# isg_eos_control_board_xem3001.net
KiCad netlist of a schematic drawn in Altium Designer
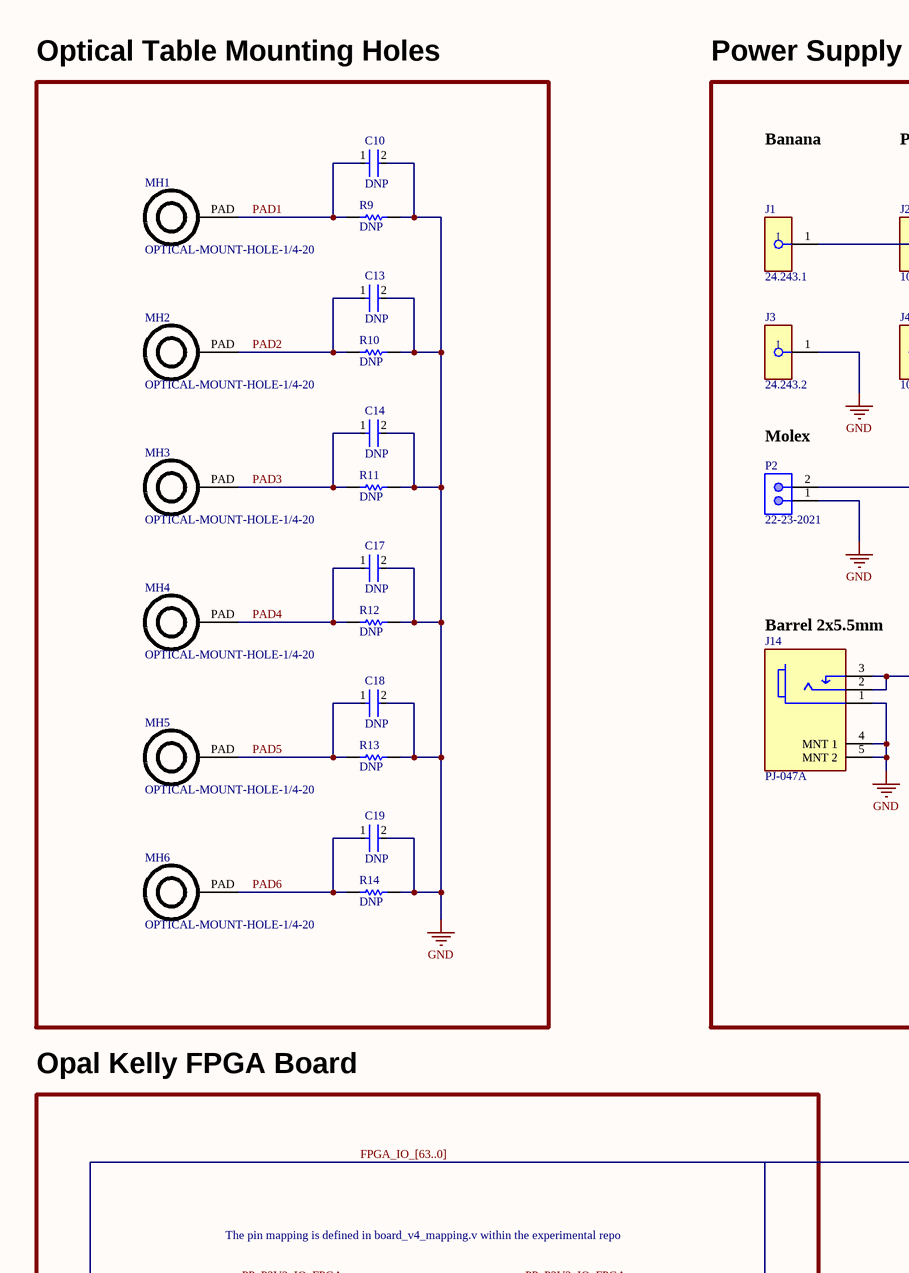
[diagram p0: isg_eos_control_board_xem3001.SchDoc, top left]
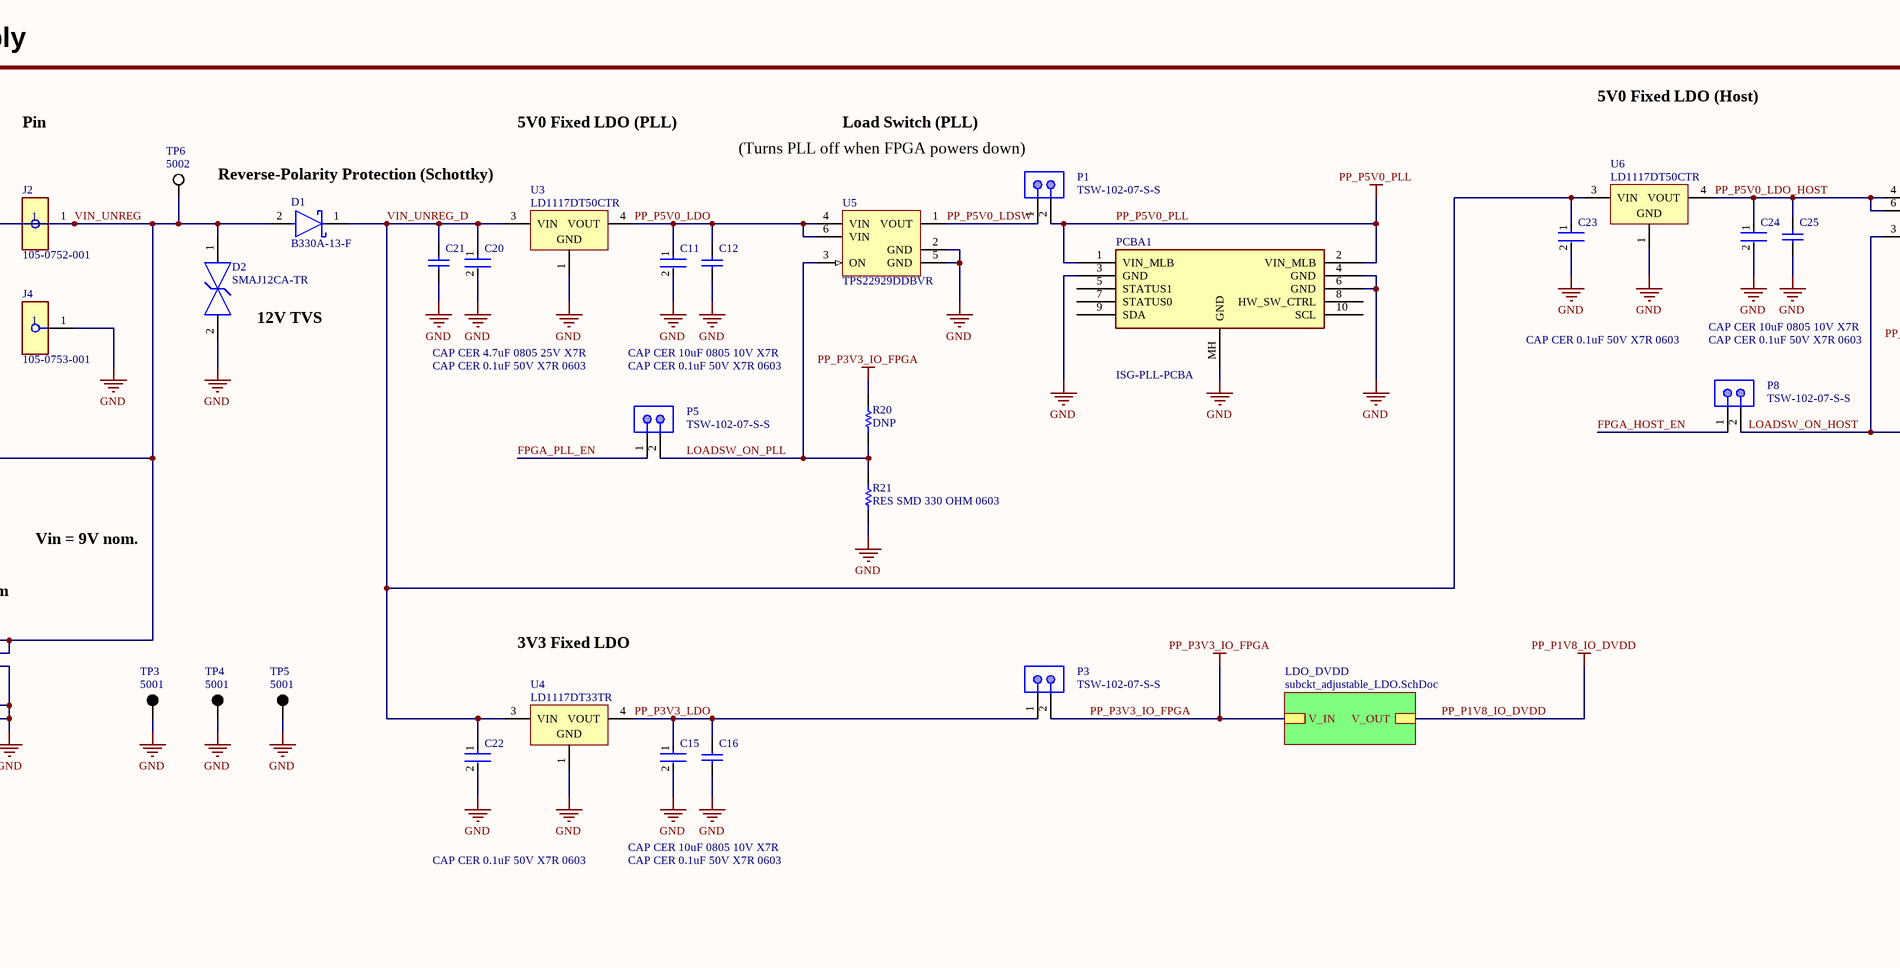
[diagram p1: isg_eos_control_board_xem3001.SchDoc, top middle]
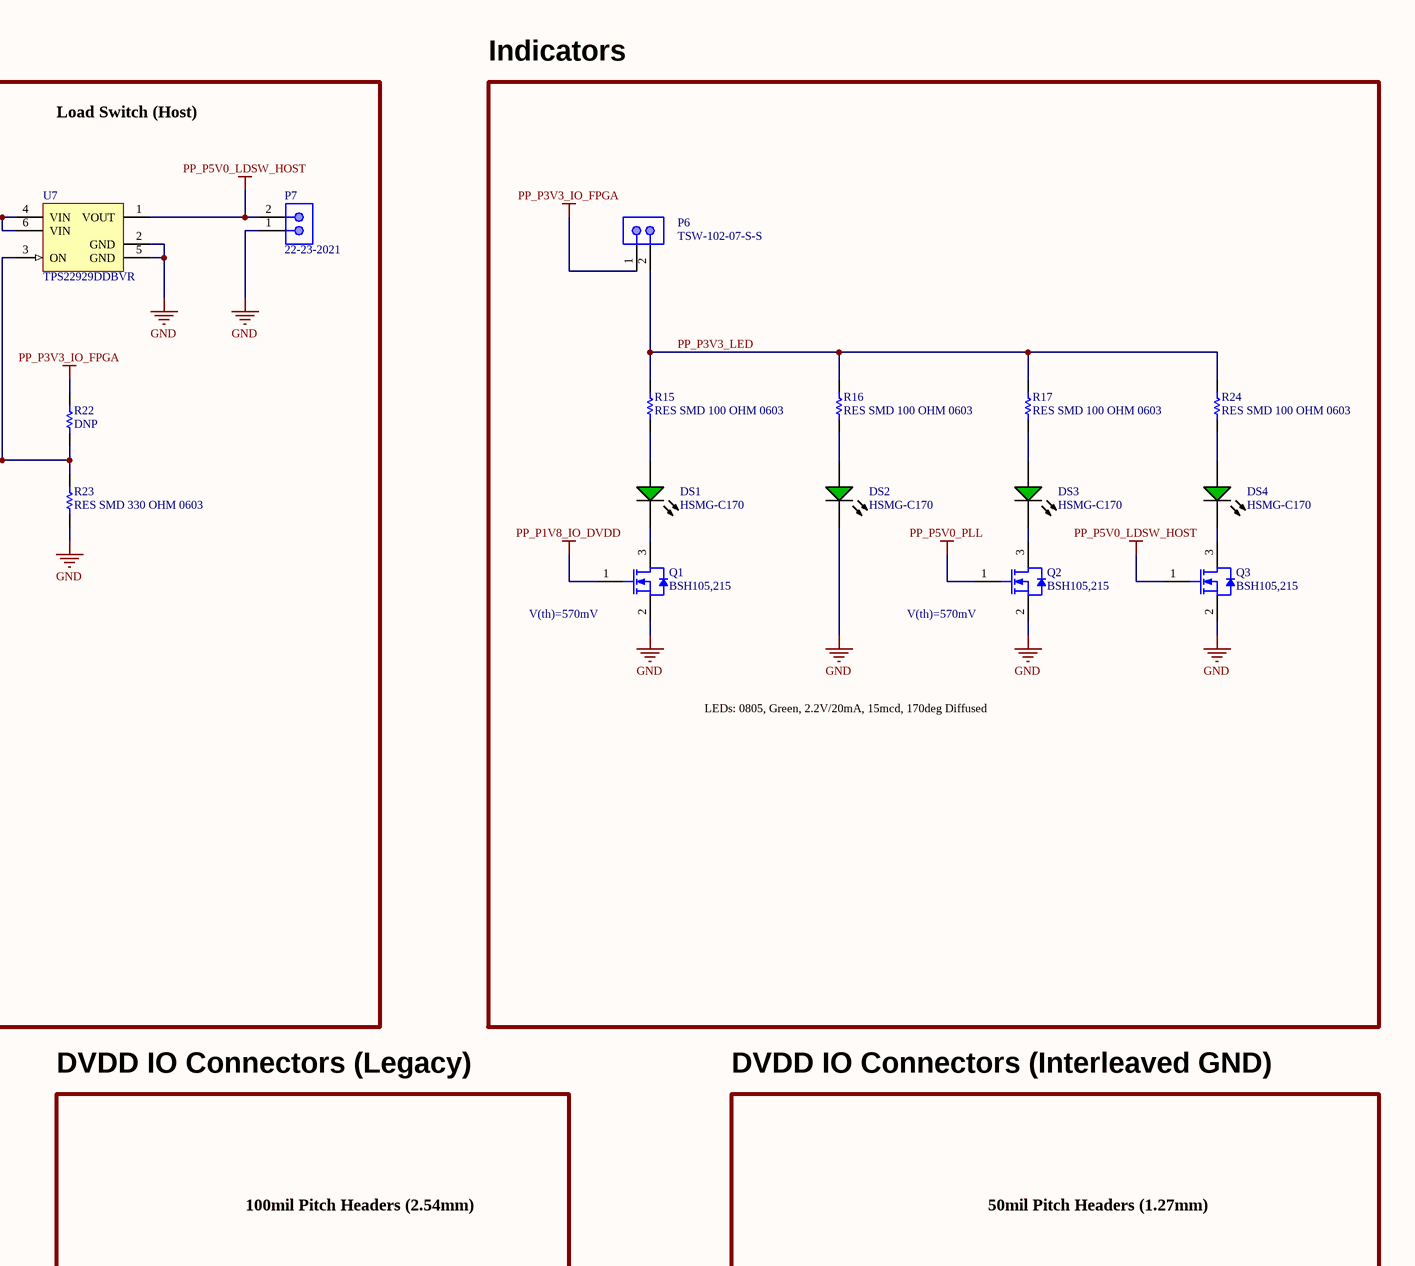
[diagram p2: isg_eos_control_board_xem3001.SchDoc, top right]
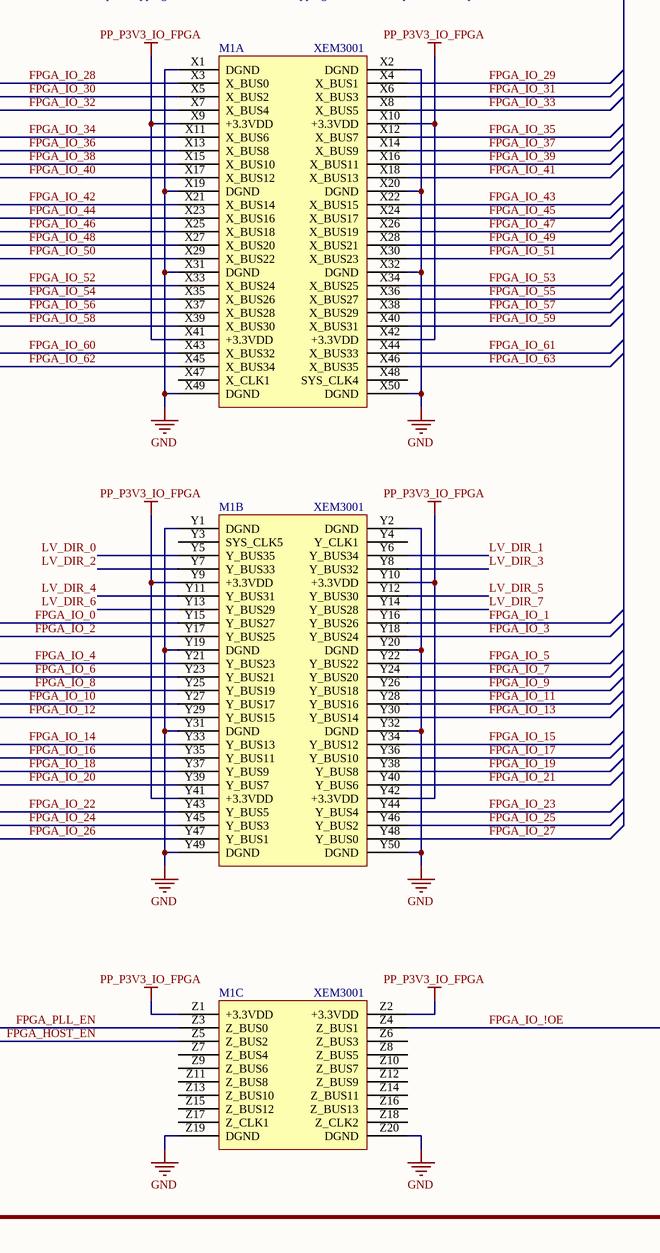
[diagram p3: isg_eos_control_board_xem3001.SchDoc, bottom left]
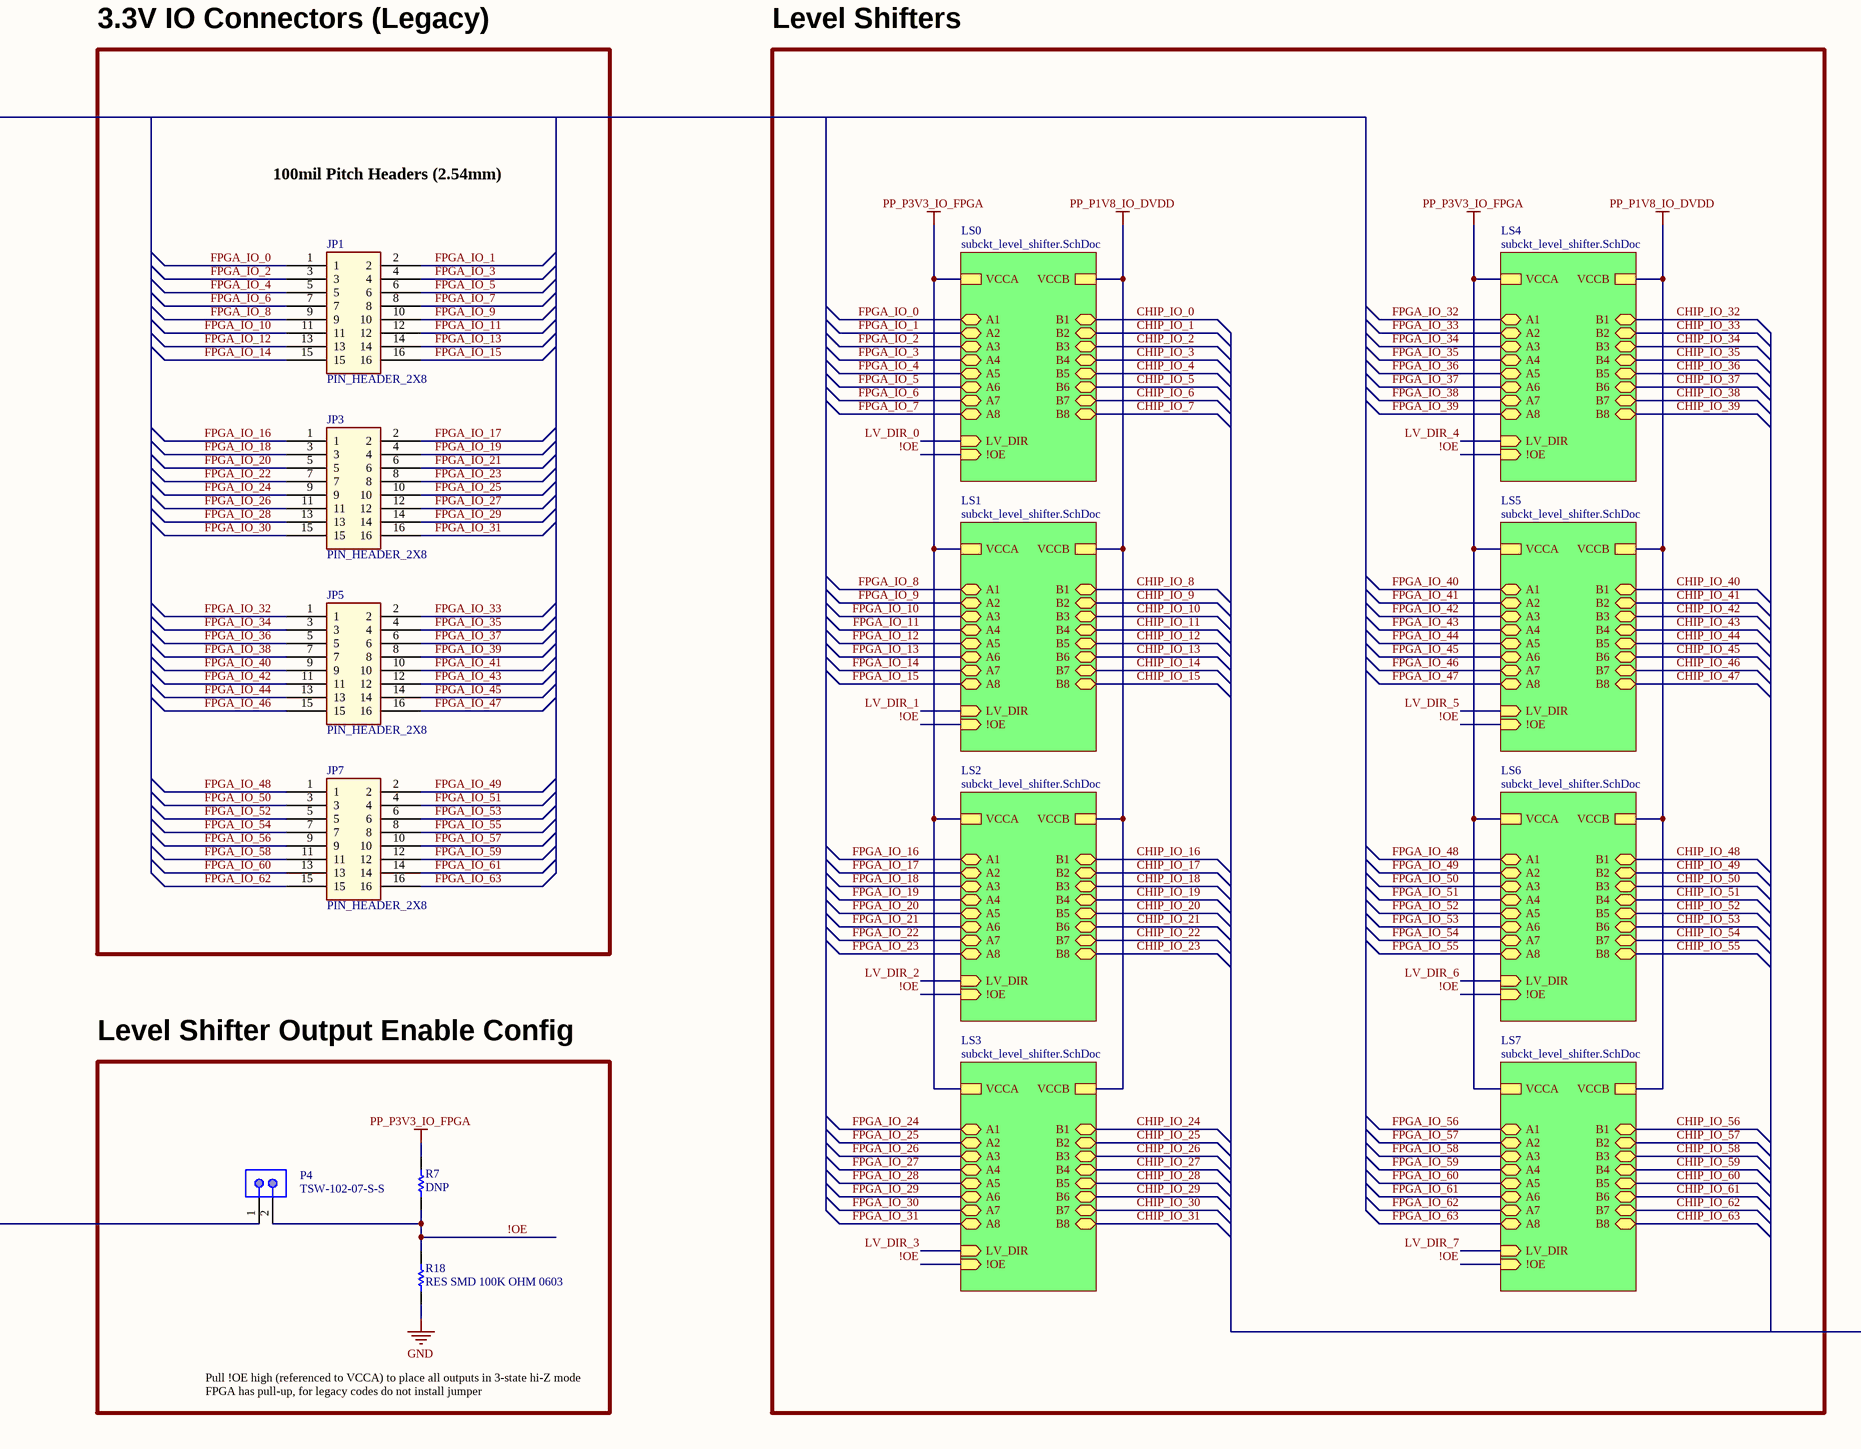
[diagram p4: isg_eos_control_board_xem3001.SchDoc, bottom middle]
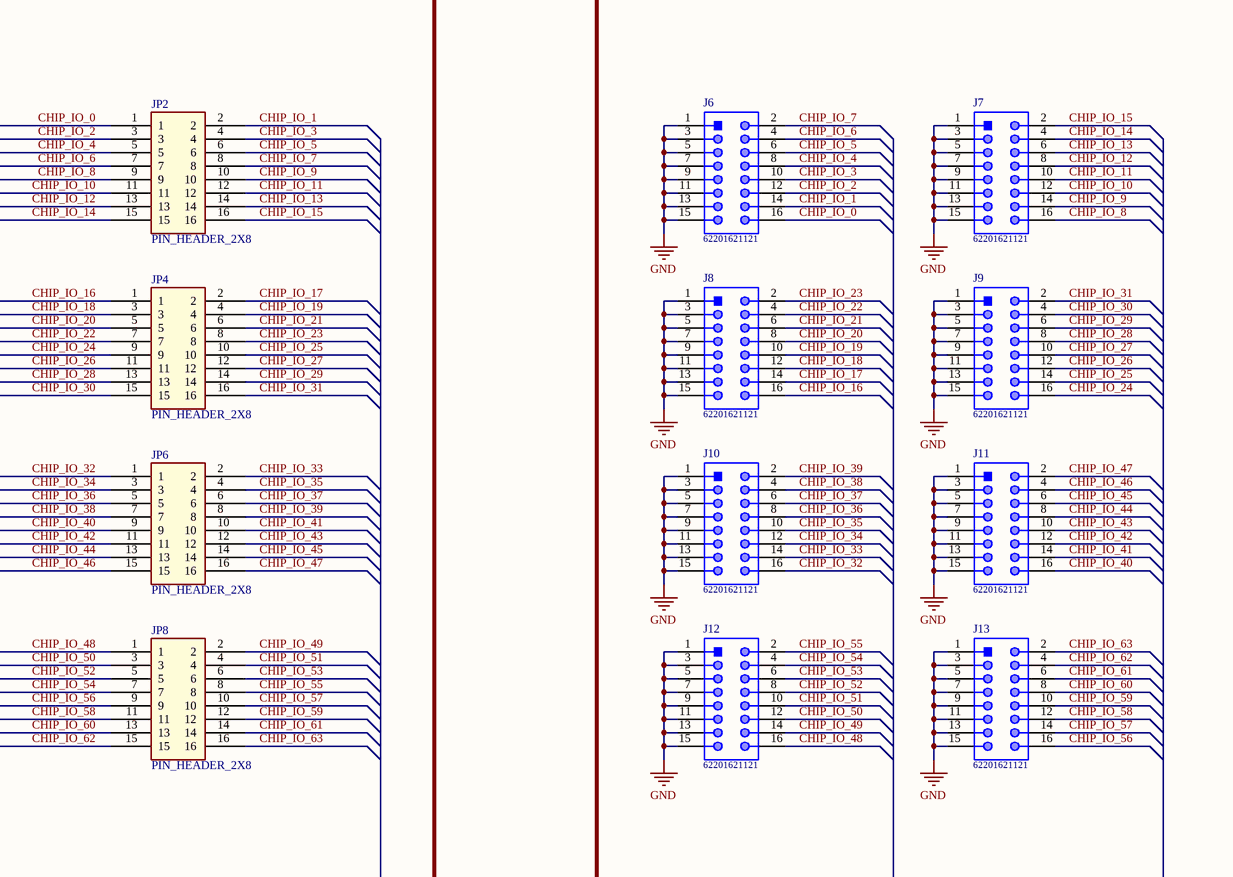
[diagram p5: isg_eos_control_board_xem3001.SchDoc, bottom right]

(export (version "E")
  (design (tool "Eeschema 10.0.6"))
  (components
    (comp (ref "C10")
      (value "DNP")
      (footprint "FP-CC0603-DA-MFG")
      (fields
        (field (name "OCTOPART") "https://octopart.com/cc0603krx7r7bb104-yageo-192941")
        (field (name "TOLERANCE") "0.1")
        (field (name "VOLTAGE") "16 V")
      )
      (libsource (lib "Altium Content Vault") (part "11868f565c42a9108669ba33697ecf6"))
    )
    (comp (ref "C11")
      (value "CAP CER 0.1uF 50V X7R 0603")
      (footprint "FP-CC0603-DA-MFG")
      (fields
        (field (name "OCTOPART") "https://octopart.com/cc0603krx7r7bb104-yageo-192941")
        (field (name "TOLERANCE") "0.1")
        (field (name "VOLTAGE") "16 V")
      )
      (libsource (lib "Altium Content Vault") (part "11868f565c42a9108669ba33697ecf6"))
    )
    (comp (ref "C12")
      (value "CAP CER 10uF 0805 10V X7R")
      (footprint "CAPC2013X140X50NL20T25")
      (fields
        (field (name "PART NUMBER") "0805ZC475KAT2A")
        (field (name "MANUFACTURER") "AVX Interconnect / Elco")
      )
      (libsource (lib "Altium Content Vault") (part "CAP"))
    )
    (comp (ref "C13")
      (value "DNP")
      (footprint "FP-CC0603-DA-MFG")
      (fields
        (field (name "OCTOPART") "https://octopart.com/cc0603krx7r7bb104-yageo-192941")
        (field (name "TOLERANCE") "0.1")
        (field (name "VOLTAGE") "16 V")
      )
      (libsource (lib "Altium Content Vault") (part "11868f565c42a9108669ba33697ecf6"))
    )
    (comp (ref "C14")
      (value "DNP")
      (footprint "FP-CC0603-DA-MFG")
      (fields
        (field (name "OCTOPART") "https://octopart.com/cc0603krx7r7bb104-yageo-192941")
        (field (name "TOLERANCE") "0.1")
        (field (name "VOLTAGE") "16 V")
      )
      (libsource (lib "Altium Content Vault") (part "11868f565c42a9108669ba33697ecf6"))
    )
    (comp (ref "C15")
      (value "CAP CER 0.1uF 50V X7R 0603")
      (footprint "FP-CC0603-DA-MFG")
      (fields
        (field (name "OCTOPART") "https://octopart.com/cc0603krx7r7bb104-yageo-192941")
        (field (name "TOLERANCE") "0.1")
        (field (name "VOLTAGE") "16 V")
      )
      (libsource (lib "Altium Content Vault") (part "11868f565c42a9108669ba33697ecf6"))
    )
    (comp (ref "C16")
      (value "CAP CER 10uF 0805 10V X7R")
      (footprint "CAPC2013X140X50NL20T25")
      (fields
        (field (name "PART NUMBER") "0805ZC475KAT2A")
        (field (name "MANUFACTURER") "AVX Interconnect / Elco")
      )
      (libsource (lib "Altium Content Vault") (part "CAP"))
    )
    (comp (ref "C17")
      (value "DNP")
      (footprint "FP-CC0603-DA-MFG")
      (fields
        (field (name "OCTOPART") "https://octopart.com/cc0603krx7r7bb104-yageo-192941")
        (field (name "TOLERANCE") "0.1")
        (field (name "VOLTAGE") "16 V")
      )
      (libsource (lib "Altium Content Vault") (part "11868f565c42a9108669ba33697ecf6"))
    )
    (comp (ref "C18")
      (value "DNP")
      (footprint "FP-CC0603-DA-MFG")
      (fields
        (field (name "OCTOPART") "https://octopart.com/cc0603krx7r7bb104-yageo-192941")
        (field (name "TOLERANCE") "0.1")
        (field (name "VOLTAGE") "16 V")
      )
      (libsource (lib "Altium Content Vault") (part "11868f565c42a9108669ba33697ecf6"))
    )
    (comp (ref "C19")
      (value "DNP")
      (footprint "FP-CC0603-DA-MFG")
      (fields
        (field (name "OCTOPART") "https://octopart.com/cc0603krx7r7bb104-yageo-192941")
        (field (name "TOLERANCE") "0.1")
        (field (name "VOLTAGE") "16 V")
      )
      (libsource (lib "Altium Content Vault") (part "11868f565c42a9108669ba33697ecf6"))
    )
    (comp (ref "C20")
      (value "CAP CER 0.1uF 50V X7R 0603")
      (footprint "FP-CC0603-DA-MFG")
      (fields
        (field (name "OCTOPART") "https://octopart.com/cc0603krx7r7bb104-yageo-192941")
        (field (name "TOLERANCE") "0.1")
        (field (name "VOLTAGE") "16 V")
      )
      (libsource (lib "Altium Content Vault") (part "11868f565c42a9108669ba33697ecf6"))
    )
    (comp (ref "C21")
      (value "CAP CER 4.7uF 0805 25V X7R")
      (footprint "CAPC2013X140X50NL20T25")
      (fields
        (field (name "PART NUMBER") "0805ZC475KAT2A")
        (field (name "MANUFACTURER") "AVX Interconnect / Elco")
      )
      (libsource (lib "Altium Content Vault") (part "CAP"))
    )
    (comp (ref "C22")
      (value "CAP CER 0.1uF 50V X7R 0603")
      (footprint "FP-CC0603-DA-MFG")
      (fields
        (field (name "OCTOPART") "https://octopart.com/cc0603krx7r7bb104-yageo-192941")
        (field (name "TOLERANCE") "0.1")
        (field (name "VOLTAGE") "16 V")
      )
      (libsource (lib "Altium Content Vault") (part "11868f565c42a9108669ba33697ecf6"))
    )
    (comp (ref "C23")
      (value "CAP CER 0.1uF 50V X7R 0603")
      (footprint "FP-CC0603-DA-MFG")
      (fields
        (field (name "OCTOPART") "https://octopart.com/cc0603krx7r7bb104-yageo-192941")
        (field (name "TOLERANCE") "0.1")
        (field (name "VOLTAGE") "16 V")
      )
      (libsource (lib "Altium Content Vault") (part "11868f565c42a9108669ba33697ecf6"))
    )
    (comp (ref "C24")
      (value "CAP CER 0.1uF 50V X7R 0603")
      (footprint "FP-CC0603-DA-MFG")
      (fields
        (field (name "OCTOPART") "https://octopart.com/cc0603krx7r7bb104-yageo-192941")
        (field (name "TOLERANCE") "0.1")
        (field (name "VOLTAGE") "16 V")
      )
      (libsource (lib "Altium Content Vault") (part "11868f565c42a9108669ba33697ecf6"))
    )
    (comp (ref "C25")
      (value "CAP CER 10uF 0805 10V X7R")
      (footprint "CAPC2013X140X50NL20T25")
      (fields
        (field (name "PART NUMBER") "0805ZC475KAT2A")
        (field (name "MANUFACTURER") "AVX Interconnect / Elco")
      )
      (libsource (lib "Altium Content Vault") (part "CAP"))
    )
    (comp (ref "D1")
      (value "B330A-13-F")
      (footprint "FP-SMA-MFG")
      (description "DIODE SCHOTTKY 30V 3A SMA")
      (fields
        (field (name "OCTOPART") "https://octopart.com/b330a-13-f-diodes+inc.-325808")
        (field (name "MANUFACTURER") "Diodes")
      )
      (libsource (lib "Altium Content Vault") (part "1d6ec82d83fb6aee721767c19dac4b9"))
    )
    (comp (ref "D2")
      (value "SMAJ12CA-TR")
      (footprint "FP-SMA-CA-MFG")
      (description "TVS DIODE 12V 25.3V SMA")
      (fields
        (field (name "OCTOPART") "https://octopart.com/smaj12ca-tr-stmicroelectronics-347060")
        (field (name "MANUFACTURER") "STMicroelectronics")
      )
      (libsource (lib "Altium Content Vault") (part "876f4347bf90aa6f500f43e3cd03972"))
    )
    (comp (ref "DS1")
      (value "HSMG-C170")
      (footprint "AVAG-HSMX-C170_V")
      (description "Chip LED, Green, 2.2 V, -40 to 85 degC, 2-Pin SMD, Pb-Free, Tape and Reel")
      (fields (field (name "MANUFACTURER") "Avago"))
      (libsource (lib "Altium Content Vault") (part "LED_GREEN_A1K2-2"))
    )
    (comp (ref "DS2")
      (value "HSMG-C170")
      (footprint "AVAG-HSMX-C170_V")
      (description "Chip LED, Green, 2.2 V, -40 to 85 degC, 2-Pin SMD, Pb-Free, Tape and Reel")
      (fields (field (name "MANUFACTURER") "Avago"))
      (libsource (lib "Altium Content Vault") (part "LED_GREEN_A1K2-2"))
    )
    (comp (ref "DS3")
      (value "HSMG-C170")
      (footprint "AVAG-HSMX-C170_V")
      (description "Chip LED, Green, 2.2 V, -40 to 85 degC, 2-Pin SMD, Pb-Free, Tape and Reel")
      (fields (field (name "MANUFACTURER") "Avago"))
      (libsource (lib "Altium Content Vault") (part "LED_GREEN_A1K2-2"))
    )
    (comp (ref "DS4")
      (value "HSMG-C170")
      (footprint "AVAG-HSMX-C170_V")
      (description "Chip LED, Green, 2.2 V, -40 to 85 degC, 2-Pin SMD, Pb-Free, Tape and Reel")
      (fields (field (name "MANUFACTURER") "Avago"))
      (libsource (lib "Altium Content Vault") (part "LED_GREEN_A1K2-2"))
    )
    (comp (ref "J1")
      (value "24.243.1")
      (footprint "FP-24_243_1-MFG")
      (description "RECEPTACLE, 20A, 4MM, PCB, SOLDER, RED")
      (fields
        (field (name "MANUFACTURER") "Multicomp")
        (field (name "OCTOPART") "https://octopart.com/24.243.1-multicomp-57101049")
      )
      (libsource (lib "Altium Content Vault") (part "98815daf2f2c152b0c43f5ab9800df6"))
    )
    (comp (ref "J2")
      (value "105-0752-001")
      (footprint "FP-105-0751-001-MFG")
      (description "CONN TIP JACK SOLDER WHITE")
      (fields
        (field (name "MANUFACTURER") "Cinch Connectivity")
        (field (name "OCTOPART") "https://octopart.com/105-0751-001-cinch+connectivity+solutions-51372833")
      )
      (libsource (lib "Altium Content Vault") (part "98815daf2f2c152b0c43f5ab9800df6"))
    )
    (comp (ref "J3")
      (value "24.243.2")
      (footprint "FP-24_243_2-MFG")
      (description "RECEPTACLE, 20A, 4MM, PCB, SOLDER, BLACK")
      (fields
        (field (name "MANUFACTURER") "Multicomp")
        (field (name "OCTOPART") "https://octopart.com/24.243.2-multicomp-57101050")
      )
      (libsource (lib "Altium Content Vault") (part "c5c826e0c4b67fe3b42ef77f2d4decc"))
    )
    (comp (ref "J4")
      (value "105-0753-001")
      (footprint "FP-105-0751-001-MFG")
      (description "CONN TIP JACK SOLDER WHITE")
      (fields
        (field (name "MANUFACTURER") "Cinch Connectivity")
        (field (name "OCTOPART") "https://octopart.com/105-0751-001-cinch+connectivity+solutions-51372833")
      )
      (libsource (lib "Altium Content Vault") (part "98815daf2f2c152b0c43f5ab9800df6"))
    )
    (comp (ref "J6")
      (value "62201621121")
      (footprint "62201621121")
      (description "THT Vertical Pin Header WR-PHD, Pitch 1.27 mm, Dual Row, 16 pins")
      (fields (field (name "MANUFACTURER") "Wurth Elektronik") (field (name "PUBLISHER") "WurthElektronik"))
      (libsource (lib "Altium Content Vault") (part "WE-CN-2P-M-R16"))
    )
    (comp (ref "J7")
      (value "62201621121")
      (footprint "62201621121")
      (description "THT Vertical Pin Header WR-PHD, Pitch 1.27 mm, Dual Row, 16 pins")
      (fields (field (name "MANUFACTURER") "Wurth Elektronik") (field (name "PUBLISHER") "WurthElektronik"))
      (libsource (lib "Altium Content Vault") (part "WE-CN-2P-M-R16"))
    )
    (comp (ref "J8")
      (value "62201621121")
      (footprint "62201621121")
      (description "THT Vertical Pin Header WR-PHD, Pitch 1.27 mm, Dual Row, 16 pins")
      (fields (field (name "MANUFACTURER") "Wurth Elektronik") (field (name "PUBLISHER") "WurthElektronik"))
      (libsource (lib "Altium Content Vault") (part "WE-CN-2P-M-R16"))
    )
    (comp (ref "J9")
      (value "62201621121")
      (footprint "62201621121")
      (description "THT Vertical Pin Header WR-PHD, Pitch 1.27 mm, Dual Row, 16 pins")
      (fields (field (name "MANUFACTURER") "Wurth Elektronik") (field (name "PUBLISHER") "WurthElektronik"))
      (libsource (lib "Altium Content Vault") (part "WE-CN-2P-M-R16"))
    )
    (comp (ref "J10")
      (value "62201621121")
      (footprint "62201621121")
      (description "THT Vertical Pin Header WR-PHD, Pitch 1.27 mm, Dual Row, 16 pins")
      (fields (field (name "MANUFACTURER") "Wurth Elektronik") (field (name "PUBLISHER") "WurthElektronik"))
      (libsource (lib "Altium Content Vault") (part "WE-CN-2P-M-R16"))
    )
    (comp (ref "J11")
      (value "62201621121")
      (footprint "62201621121")
      (description "THT Vertical Pin Header WR-PHD, Pitch 1.27 mm, Dual Row, 16 pins")
      (fields (field (name "MANUFACTURER") "Wurth Elektronik") (field (name "PUBLISHER") "WurthElektronik"))
      (libsource (lib "Altium Content Vault") (part "WE-CN-2P-M-R16"))
    )
    (comp (ref "J12")
      (value "62201621121")
      (footprint "62201621121")
      (description "THT Vertical Pin Header WR-PHD, Pitch 1.27 mm, Dual Row, 16 pins")
      (fields (field (name "MANUFACTURER") "Wurth Elektronik") (field (name "PUBLISHER") "WurthElektronik"))
      (libsource (lib "Altium Content Vault") (part "WE-CN-2P-M-R16"))
    )
    (comp (ref "J13")
      (value "62201621121")
      (footprint "62201621121")
      (description "THT Vertical Pin Header WR-PHD, Pitch 1.27 mm, Dual Row, 16 pins")
      (fields (field (name "MANUFACTURER") "Wurth Elektronik") (field (name "PUBLISHER") "WurthElektronik"))
      (libsource (lib "Altium Content Vault") (part "WE-CN-2P-M-R16"))
    )
    (comp (ref "J14")
      (value "PJ-047A")
      (footprint "FP-PJ-047A-MFG")
      (description "CONN PWR JACK 2X5.5MM SOLDER")
      (fields
        (field (name "OCTOPART") "https://octopart.com/pj-047a-cui-19052783")
        (field (name "MANUFACTURER") "CUI Inc")
      )
      (libsource (lib "Altium Content Vault") (part "9d5a6e3f93a3d72684d180f63c174c0"))
    )
    (comp (ref "JP1")
      (value "PIN_HEADER_2X8")
      (footprint "PIN_HEADER_2X8_2.54MM")
      (libsource (lib "headers") (part "PIN_HEADER_2X8"))
    )
    (comp (ref "JP2")
      (value "PIN_HEADER_2X8")
      (footprint "PIN_HEADER_2X8_2.54MM")
      (libsource (lib "headers") (part "PIN_HEADER_2X8"))
    )
    (comp (ref "JP3")
      (value "PIN_HEADER_2X8")
      (footprint "PIN_HEADER_2X8_2.54MM")
      (libsource (lib "headers") (part "PIN_HEADER_2X8"))
    )
    (comp (ref "JP4")
      (value "PIN_HEADER_2X8")
      (footprint "PIN_HEADER_2X8_2.54MM")
      (libsource (lib "headers") (part "PIN_HEADER_2X8"))
    )
    (comp (ref "JP5")
      (value "PIN_HEADER_2X8")
      (footprint "PIN_HEADER_2X8_2.54MM")
      (libsource (lib "headers") (part "PIN_HEADER_2X8"))
    )
    (comp (ref "JP6")
      (value "PIN_HEADER_2X8")
      (footprint "PIN_HEADER_2X8_2.54MM")
      (libsource (lib "headers") (part "PIN_HEADER_2X8"))
    )
    (comp (ref "JP7")
      (value "PIN_HEADER_2X8")
      (footprint "PIN_HEADER_2X8_2.54MM")
      (libsource (lib "headers") (part "PIN_HEADER_2X8"))
    )
    (comp (ref "JP8")
      (value "PIN_HEADER_2X8")
      (footprint "PIN_HEADER_2X8_2.54MM")
      (libsource (lib "headers") (part "PIN_HEADER_2X8"))
    )
    (comp (ref "M1")
      (value "XEM3001")
      (footprint "XEM3001MODULE")
      (description "XEM3001 Module Connector")
      (fields (field (name "MANUFACTURER") "Generic Components") (field (name "PUBLISHER") "Opal Kelly"))
      (libsource (lib "RAM3001") (part "XEM3001"))
    )
    (comp (ref "MH1")
      (value "OPTICAL-MOUNT-HOLE-1/4-20")
      (footprint "mechanical:MH-1/4-20")
      (libsource (lib "mechanical") (part "OPTICAL-MOUNT-HOLE-1/4-20"))
    )
    (comp (ref "MH2")
      (value "OPTICAL-MOUNT-HOLE-1/4-20")
      (footprint "mechanical:MH-1/4-20")
      (libsource (lib "mechanical") (part "OPTICAL-MOUNT-HOLE-1/4-20"))
    )
    (comp (ref "MH3")
      (value "OPTICAL-MOUNT-HOLE-1/4-20")
      (footprint "mechanical:MH-1/4-20")
      (libsource (lib "mechanical") (part "OPTICAL-MOUNT-HOLE-1/4-20"))
    )
    (comp (ref "MH4")
      (value "OPTICAL-MOUNT-HOLE-1/4-20")
      (footprint "mechanical:MH-1/4-20")
      (libsource (lib "mechanical") (part "OPTICAL-MOUNT-HOLE-1/4-20"))
    )
    (comp (ref "MH5")
      (value "OPTICAL-MOUNT-HOLE-1/4-20")
      (footprint "mechanical:MH-1/4-20")
      (libsource (lib "mechanical") (part "OPTICAL-MOUNT-HOLE-1/4-20"))
    )
    (comp (ref "MH6")
      (value "OPTICAL-MOUNT-HOLE-1/4-20")
      (footprint "mechanical:MH-1/4-20")
      (libsource (lib "mechanical") (part "OPTICAL-MOUNT-HOLE-1/4-20"))
    )
    (comp (ref "P1")
      (value "TSW-102-07-S-S")
      (footprint "SMTC-TSW-102-07-S-S")
      (fields (field (name "MANUFACTURER") "Samtec"))
      (libsource (lib "Altium Content Vault") (part "CN-1P-M-R2"))
    )
    (comp (ref "P2")
      (value "22-23-2021")
      (footprint "MOLX-22-23-2021_V")
      (libsource (lib "") (part "CN-1P-M-R2_1"))
    )
    (comp (ref "P3")
      (value "TSW-102-07-S-S")
      (footprint "SMTC-TSW-102-07-S-S")
      (fields (field (name "MANUFACTURER") "Samtec"))
      (libsource (lib "Altium Content Vault") (part "CN-1P-M-R2"))
    )
    (comp (ref "P4")
      (value "TSW-102-07-S-S")
      (footprint "SMTC-TSW-102-07-S-S")
      (fields (field (name "MANUFACTURER") "Samtec"))
      (libsource (lib "Altium Content Vault") (part "CN-1P-M-R2"))
    )
    (comp (ref "P5")
      (value "TSW-102-07-S-S")
      (footprint "SMTC-TSW-102-07-S-S")
      (fields (field (name "MANUFACTURER") "Samtec"))
      (libsource (lib "Altium Content Vault") (part "CN-1P-M-R2"))
    )
    (comp (ref "P6")
      (value "TSW-102-07-S-S")
      (footprint "SMTC-TSW-102-07-S-S")
      (fields (field (name "MANUFACTURER") "Samtec"))
      (libsource (lib "Altium Content Vault") (part "CN-1P-M-R2"))
    )
    (comp (ref "P7")
      (value "22-23-2021")
      (footprint "MOLX-22-23-2021_V")
      (libsource (lib "Altium Content Vault") (part "CN-1P-M-R2"))
    )
    (comp (ref "P8")
      (value "TSW-102-07-S-S")
      (footprint "SMTC-TSW-102-07-S-S")
      (fields (field (name "MANUFACTURER") "Samtec"))
      (libsource (lib "Altium Content Vault") (part "CN-1P-M-R2"))
    )
    (comp (ref "PCBA1")
      (value "ISG-PLL-PCBA")
      (footprint "ISG-PLL-PCBA")
      (libsource (lib "ISG-PLL-PCBA") (part "ISG-PLL-PCBA"))
    )
    (comp (ref "Q1")
      (value "BSH105,215")
      (footprint "NXP-SOT23_M")
      (fields (field (name "MANUFACTURER") "NXP Semiconductors"))
      (libsource (lib "Altium Content Vault") (part "NXP-NMOS-GSD-3_B"))
    )
    (comp (ref "Q2")
      (value "BSH105,215")
      (footprint "NXP-SOT23_M")
      (fields (field (name "MANUFACTURER") "NXP Semiconductors"))
      (libsource (lib "Altium Content Vault") (part "NXP-NMOS-GSD-3_B"))
    )
    (comp (ref "Q3")
      (value "BSH105,215")
      (footprint "NXP-SOT23_M")
      (fields (field (name "MANUFACTURER") "NXP Semiconductors"))
      (libsource (lib "Altium Content Vault") (part "NXP-NMOS-GSD-3_B"))
    )
    (comp (ref "R7")
      (value "DNP")
      (footprint "RESC1609X50X30LL10T20")
      (fields (field (name "PART NUMBER") "CRCW0603100KFKEA") (field (name "MANUFACTURER") "Vishay Dale"))
      (libsource (lib "Altium Content Vault") (part "RES"))
    )
    (comp (ref "R9")
      (value "DNP")
      (footprint "RESC1609X50X30LL10T20")
      (fields (field (name "PART NUMBER") "CRCW0603100KFKEA") (field (name "MANUFACTURER") "Vishay Dale"))
      (libsource (lib "Altium Content Vault") (part "RES"))
    )
    (comp (ref "R10")
      (value "DNP")
      (footprint "RESC1609X50X30LL10T20")
      (fields (field (name "PART NUMBER") "CRCW0603100KFKEA") (field (name "MANUFACTURER") "Vishay Dale"))
      (libsource (lib "Altium Content Vault") (part "RES"))
    )
    (comp (ref "R11")
      (value "DNP")
      (footprint "RESC1609X50X30LL10T20")
      (fields (field (name "PART NUMBER") "CRCW0603100KFKEA") (field (name "MANUFACTURER") "Vishay Dale"))
      (libsource (lib "Altium Content Vault") (part "RES"))
    )
    (comp (ref "R12")
      (value "DNP")
      (footprint "RESC1609X50X30LL10T20")
      (fields (field (name "PART NUMBER") "CRCW0603100KFKEA") (field (name "MANUFACTURER") "Vishay Dale"))
      (libsource (lib "Altium Content Vault") (part "RES"))
    )
    (comp (ref "R13")
      (value "DNP")
      (footprint "RESC1609X50X30LL10T20")
      (fields (field (name "PART NUMBER") "CRCW0603100KFKEA") (field (name "MANUFACTURER") "Vishay Dale"))
      (libsource (lib "Altium Content Vault") (part "RES"))
    )
    (comp (ref "R14")
      (value "DNP")
      (footprint "RESC1609X50X30LL10T20")
      (fields (field (name "PART NUMBER") "CRCW0603100KFKEA") (field (name "MANUFACTURER") "Vishay Dale"))
      (libsource (lib "Altium Content Vault") (part "RES"))
    )
    (comp (ref "R15")
      (value "RES SMD 100 OHM 0603")
      (footprint "RESC1609X50X30LL10T20")
      (fields (field (name "PART NUMBER") "CRCW0603100KFKEA") (field (name "MANUFACTURER") "Vishay Dale"))
      (libsource (lib "Altium Content Vault") (part "RES"))
    )
    (comp (ref "R16")
      (value "RES SMD 100 OHM 0603")
      (footprint "RESC1609X50X30LL10T20")
      (fields (field (name "PART NUMBER") "CRCW0603100KFKEA") (field (name "MANUFACTURER") "Vishay Dale"))
      (libsource (lib "Altium Content Vault") (part "RES"))
    )
    (comp (ref "R17")
      (value "RES SMD 100 OHM 0603")
      (footprint "RESC1609X50X30LL10T20")
      (fields (field (name "PART NUMBER") "CRCW0603100KFKEA") (field (name "MANUFACTURER") "Vishay Dale"))
      (libsource (lib "Altium Content Vault") (part "RES"))
    )
    (comp (ref "R18")
      (value "RES SMD 100K OHM 0603")
      (footprint "RESC1609X50X30LL10T20")
      (fields (field (name "PART NUMBER") "CRCW0603100KFKEA") (field (name "MANUFACTURER") "Vishay Dale"))
      (libsource (lib "Altium Content Vault") (part "RES"))
    )
    (comp (ref "R20")
      (value "DNP")
      (footprint "RESC1609X50X30LL10T20")
      (fields (field (name "PART NUMBER") "CRCW0603100KFKEA") (field (name "MANUFACTURER") "Vishay Dale"))
      (libsource (lib "Altium Content Vault") (part "RES"))
    )
    (comp (ref "R21")
      (value "RES SMD 330 OHM 0603")
      (footprint "RESC1609X50X30LL10T20")
      (fields (field (name "PART NUMBER") "CRCW0603100KFKEA") (field (name "MANUFACTURER") "Vishay Dale"))
      (libsource (lib "Altium Content Vault") (part "RES"))
    )
    (comp (ref "R22")
      (value "DNP")
      (footprint "RESC1609X50X30LL10T20")
      (fields (field (name "PART NUMBER") "CRCW0603100KFKEA") (field (name "MANUFACTURER") "Vishay Dale"))
      (libsource (lib "Altium Content Vault") (part "RES"))
    )
    (comp (ref "R23")
      (value "RES SMD 330 OHM 0603")
      (footprint "RESC1609X50X30LL10T20")
      (fields (field (name "PART NUMBER") "CRCW0603100KFKEA") (field (name "MANUFACTURER") "Vishay Dale"))
      (libsource (lib "Altium Content Vault") (part "RES"))
    )
    (comp (ref "R24")
      (value "RES SMD 100 OHM 0603")
      (footprint "RESC1609X50X30LL10T20")
      (fields (field (name "PART NUMBER") "CRCW0603100KFKEA") (field (name "MANUFACTURER") "Vishay Dale"))
      (libsource (lib "Altium Content Vault") (part "RES"))
    )
    (comp (ref "TP3")
      (value "5001")
      (footprint "KSTN-5001")
      (description "Test Point, Black, 1-Pin THD, RoHS, Bulk")
      (fields (field (name "MANUFACTURER") "Keystone"))
      (libsource (lib "Altium Content Vault") (part "KSTN-TP-5001"))
    )
    (comp (ref "TP4")
      (value "5001")
      (footprint "KSTN-5001")
      (description "Test Point, Black, 1-Pin THD, RoHS, Bulk")
      (fields (field (name "MANUFACTURER") "Keystone"))
      (libsource (lib "Altium Content Vault") (part "KSTN-TP-5001"))
    )
    (comp (ref "TP5")
      (value "5001")
      (footprint "KSTN-5001")
      (description "Test Point, Black, 1-Pin THD, RoHS, Bulk")
      (fields (field (name "MANUFACTURER") "Keystone"))
      (libsource (lib "Altium Content Vault") (part "KSTN-TP-5001"))
    )
    (comp (ref "TP6")
      (value "5002")
      (footprint "KSTN-5002")
      (description "Test Point, White, 1-Pin THD, RoHS, Bulk")
      (fields (field (name "MANUFACTURER") "KeystoneElectronics"))
      (libsource (lib "Altium Content Vault") (part "KSTN-TP-5002"))
    )
    (comp (ref "U3")
      (value "LD1117DT50CTR")
      (footprint "TO-252_N")
      (description "Fixed Low Drop Positive Voltage Regulator, 5V, 3-Pin DPAK, Tape and Reel")
      (libsource (lib "Altium Content Vault") (part "PM-REG-LD1117-SOT3"))
    )
    (comp (ref "U4")
      (value "LD1117DT33TR")
      (footprint "TO-252_N")
      (description "Fixed Low Drop Positive Voltage Regulator, 3.3V, 3-Pin DPAK, Tape and Reel")
      (libsource (lib "Altium Content Vault") (part "PM-REG-LD1117-SOT3"))
    )
    (comp (ref "U5")
      (value "TPS22929DDBVR")
      (footprint "DBV0006A_M")
      (fields (field (name "MANUFACTURER") "Texas Instruments"))
      (libsource (lib "Altium Content Vault") (part "TI-TPS22929DDBV6"))
    )
    (comp (ref "U6")
      (value "LD1117DT50CTR")
      (footprint "TO-252_N")
      (description "Fixed Low Drop Positive Voltage Regulator, 5V, 3-Pin DPAK, Tape and Reel")
      (libsource (lib "Altium Content Vault") (part "PM-REG-LD1117-SOT3"))
    )
    (comp (ref "U7")
      (value "TPS22929DDBVR")
      (footprint "DBV0006A_M")
      (fields (field (name "MANUFACTURER") "Texas Instruments"))
      (libsource (lib "Altium Content Vault") (part "TI-TPS22929DDBV6"))
    )
  )
  (nets
    (net (code "1") (name "/!OE") (class "Default")
      (node (ref "P4") (pin "2") (pinfunction "2_2") (pintype "passive"))
      (node (ref "R18") (pin "1") (pinfunction "1_1") (pintype "passive"))
      (node (ref "R7") (pin "2") (pinfunction "2_2") (pintype "passive"))
    )
    (net (code "2") (name "/CHIP_IO_0") (class "Default")
      (node (ref "J6") (pin "16") (pinfunction "16_16") (pintype "passive"))
      (node (ref "JP2") (pin "1") (pinfunction "1_1") (pintype "passive"))
    )
    (net (code "3") (name "/CHIP_IO_1") (class "Default")
      (node (ref "J6") (pin "14") (pinfunction "14_14") (pintype "passive"))
      (node (ref "JP2") (pin "2") (pinfunction "2_2") (pintype "passive"))
    )
    (net (code "4") (name "/CHIP_IO_2") (class "Default")
      (node (ref "J6") (pin "12") (pinfunction "12_12") (pintype "passive"))
      (node (ref "JP2") (pin "3") (pinfunction "3_3") (pintype "passive"))
    )
    (net (code "5") (name "/CHIP_IO_3") (class "Default")
      (node (ref "J6") (pin "10") (pinfunction "10_10") (pintype "passive"))
      (node (ref "JP2") (pin "4") (pinfunction "4_4") (pintype "passive"))
    )
    (net (code "6") (name "/CHIP_IO_4") (class "Default")
      (node (ref "J6") (pin "8") (pinfunction "8_8") (pintype "passive"))
      (node (ref "JP2") (pin "5") (pinfunction "5_5") (pintype "passive"))
    )
    (net (code "7") (name "/CHIP_IO_5") (class "Default")
      (node (ref "J6") (pin "6") (pinfunction "6_6") (pintype "passive"))
      (node (ref "JP2") (pin "6") (pinfunction "6_6") (pintype "passive"))
    )
    (net (code "8") (name "/CHIP_IO_6") (class "Default")
      (node (ref "J6") (pin "4") (pinfunction "4_4") (pintype "passive"))
      (node (ref "JP2") (pin "7") (pinfunction "7_7") (pintype "passive"))
    )
    (net (code "9") (name "/CHIP_IO_7") (class "Default")
      (node (ref "J6") (pin "2") (pinfunction "2_2") (pintype "passive"))
      (node (ref "JP2") (pin "8") (pinfunction "8_8") (pintype "passive"))
    )
    (net (code "10") (name "/CHIP_IO_8") (class "Default")
      (node (ref "J7") (pin "16") (pinfunction "16_16") (pintype "passive"))
      (node (ref "JP2") (pin "9") (pinfunction "9_9") (pintype "passive"))
    )
    (net (code "11") (name "/CHIP_IO_9") (class "Default")
      (node (ref "J7") (pin "14") (pinfunction "14_14") (pintype "passive"))
      (node (ref "JP2") (pin "10") (pinfunction "10_10") (pintype "passive"))
    )
    (net (code "12") (name "/CHIP_IO_10") (class "Default")
      (node (ref "J7") (pin "12") (pinfunction "12_12") (pintype "passive"))
      (node (ref "JP2") (pin "11") (pinfunction "11_11") (pintype "passive"))
    )
    (net (code "13") (name "/CHIP_IO_11") (class "Default")
      (node (ref "J7") (pin "10") (pinfunction "10_10") (pintype "passive"))
      (node (ref "JP2") (pin "12") (pinfunction "12_12") (pintype "passive"))
    )
    (net (code "14") (name "/CHIP_IO_12") (class "Default")
      (node (ref "J7") (pin "8") (pinfunction "8_8") (pintype "passive"))
      (node (ref "JP2") (pin "13") (pinfunction "13_13") (pintype "passive"))
    )
    (net (code "15") (name "/CHIP_IO_13") (class "Default")
      (node (ref "J7") (pin "6") (pinfunction "6_6") (pintype "passive"))
      (node (ref "JP2") (pin "14") (pinfunction "14_14") (pintype "passive"))
    )
    (net (code "16") (name "/CHIP_IO_14") (class "Default")
      (node (ref "J7") (pin "4") (pinfunction "4_4") (pintype "passive"))
      (node (ref "JP2") (pin "15") (pinfunction "15_15") (pintype "passive"))
    )
    (net (code "17") (name "/CHIP_IO_15") (class "Default")
      (node (ref "J7") (pin "2") (pinfunction "2_2") (pintype "passive"))
      (node (ref "JP2") (pin "16") (pinfunction "16_16") (pintype "passive"))
    )
    (net (code "18") (name "/CHIP_IO_16") (class "Default")
      (node (ref "J8") (pin "16") (pinfunction "16_16") (pintype "passive"))
      (node (ref "JP4") (pin "1") (pinfunction "1_1") (pintype "passive"))
    )
    (net (code "19") (name "/CHIP_IO_17") (class "Default")
      (node (ref "J8") (pin "14") (pinfunction "14_14") (pintype "passive"))
      (node (ref "JP4") (pin "2") (pinfunction "2_2") (pintype "passive"))
    )
    (net (code "20") (name "/CHIP_IO_18") (class "Default")
      (node (ref "J8") (pin "12") (pinfunction "12_12") (pintype "passive"))
      (node (ref "JP4") (pin "3") (pinfunction "3_3") (pintype "passive"))
    )
    (net (code "21") (name "/CHIP_IO_19") (class "Default")
      (node (ref "J8") (pin "10") (pinfunction "10_10") (pintype "passive"))
      (node (ref "JP4") (pin "4") (pinfunction "4_4") (pintype "passive"))
    )
    (net (code "22") (name "/CHIP_IO_20") (class "Default")
      (node (ref "J8") (pin "8") (pinfunction "8_8") (pintype "passive"))
      (node (ref "JP4") (pin "5") (pinfunction "5_5") (pintype "passive"))
    )
    (net (code "23") (name "/CHIP_IO_21") (class "Default")
      (node (ref "J8") (pin "6") (pinfunction "6_6") (pintype "passive"))
      (node (ref "JP4") (pin "6") (pinfunction "6_6") (pintype "passive"))
    )
    (net (code "24") (name "/CHIP_IO_22") (class "Default")
      (node (ref "J8") (pin "4") (pinfunction "4_4") (pintype "passive"))
      (node (ref "JP4") (pin "7") (pinfunction "7_7") (pintype "passive"))
    )
    (net (code "25") (name "/CHIP_IO_23") (class "Default")
      (node (ref "J8") (pin "2") (pinfunction "2_2") (pintype "passive"))
      (node (ref "JP4") (pin "8") (pinfunction "8_8") (pintype "passive"))
    )
    (net (code "26") (name "/CHIP_IO_24") (class "Default")
      (node (ref "J9") (pin "16") (pinfunction "16_16") (pintype "passive"))
      (node (ref "JP4") (pin "9") (pinfunction "9_9") (pintype "passive"))
    )
    (net (code "27") (name "/CHIP_IO_25") (class "Default")
      (node (ref "J9") (pin "14") (pinfunction "14_14") (pintype "passive"))
      (node (ref "JP4") (pin "10") (pinfunction "10_10") (pintype "passive"))
    )
    (net (code "28") (name "/CHIP_IO_26") (class "Default")
      (node (ref "J9") (pin "12") (pinfunction "12_12") (pintype "passive"))
      (node (ref "JP4") (pin "11") (pinfunction "11_11") (pintype "passive"))
    )
    (net (code "29") (name "/CHIP_IO_27") (class "Default")
      (node (ref "J9") (pin "10") (pinfunction "10_10") (pintype "passive"))
      (node (ref "JP4") (pin "12") (pinfunction "12_12") (pintype "passive"))
    )
    (net (code "30") (name "/CHIP_IO_28") (class "Default")
      (node (ref "J9") (pin "8") (pinfunction "8_8") (pintype "passive"))
      (node (ref "JP4") (pin "13") (pinfunction "13_13") (pintype "passive"))
    )
    (net (code "31") (name "/CHIP_IO_29") (class "Default")
      (node (ref "J9") (pin "6") (pinfunction "6_6") (pintype "passive"))
      (node (ref "JP4") (pin "14") (pinfunction "14_14") (pintype "passive"))
    )
    (net (code "32") (name "/CHIP_IO_30") (class "Default")
      (node (ref "J9") (pin "4") (pinfunction "4_4") (pintype "passive"))
      (node (ref "JP4") (pin "15") (pinfunction "15_15") (pintype "passive"))
    )
    (net (code "33") (name "/CHIP_IO_31") (class "Default")
      (node (ref "J9") (pin "2") (pinfunction "2_2") (pintype "passive"))
      (node (ref "JP4") (pin "16") (pinfunction "16_16") (pintype "passive"))
    )
    (net (code "34") (name "/CHIP_IO_32") (class "Default")
      (node (ref "J10") (pin "16") (pinfunction "16_16") (pintype "passive"))
      (node (ref "JP6") (pin "1") (pinfunction "1_1") (pintype "passive"))
    )
    (net (code "35") (name "/CHIP_IO_33") (class "Default")
      (node (ref "J10") (pin "14") (pinfunction "14_14") (pintype "passive"))
      (node (ref "JP6") (pin "2") (pinfunction "2_2") (pintype "passive"))
    )
    (net (code "36") (name "/CHIP_IO_34") (class "Default")
      (node (ref "J10") (pin "12") (pinfunction "12_12") (pintype "passive"))
      (node (ref "JP6") (pin "3") (pinfunction "3_3") (pintype "passive"))
    )
    (net (code "37") (name "/CHIP_IO_35") (class "Default")
      (node (ref "J10") (pin "10") (pinfunction "10_10") (pintype "passive"))
      (node (ref "JP6") (pin "4") (pinfunction "4_4") (pintype "passive"))
    )
    (net (code "38") (name "/CHIP_IO_36") (class "Default")
      (node (ref "J10") (pin "8") (pinfunction "8_8") (pintype "passive"))
      (node (ref "JP6") (pin "5") (pinfunction "5_5") (pintype "passive"))
    )
    (net (code "39") (name "/CHIP_IO_37") (class "Default")
      (node (ref "J10") (pin "6") (pinfunction "6_6") (pintype "passive"))
      (node (ref "JP6") (pin "6") (pinfunction "6_6") (pintype "passive"))
    )
    (net (code "40") (name "/CHIP_IO_38") (class "Default")
      (node (ref "J10") (pin "4") (pinfunction "4_4") (pintype "passive"))
      (node (ref "JP6") (pin "7") (pinfunction "7_7") (pintype "passive"))
    )
    (net (code "41") (name "/CHIP_IO_39") (class "Default")
      (node (ref "J10") (pin "2") (pinfunction "2_2") (pintype "passive"))
      (node (ref "JP6") (pin "8") (pinfunction "8_8") (pintype "passive"))
    )
    (net (code "42") (name "/CHIP_IO_40") (class "Default")
      (node (ref "J11") (pin "16") (pinfunction "16_16") (pintype "passive"))
      (node (ref "JP6") (pin "9") (pinfunction "9_9") (pintype "passive"))
    )
    (net (code "43") (name "/CHIP_IO_41") (class "Default")
      (node (ref "J11") (pin "14") (pinfunction "14_14") (pintype "passive"))
      (node (ref "JP6") (pin "10") (pinfunction "10_10") (pintype "passive"))
    )
    (net (code "44") (name "/CHIP_IO_42") (class "Default")
      (node (ref "J11") (pin "12") (pinfunction "12_12") (pintype "passive"))
      (node (ref "JP6") (pin "11") (pinfunction "11_11") (pintype "passive"))
    )
    (net (code "45") (name "/CHIP_IO_43") (class "Default")
      (node (ref "J11") (pin "10") (pinfunction "10_10") (pintype "passive"))
      (node (ref "JP6") (pin "12") (pinfunction "12_12") (pintype "passive"))
    )
    (net (code "46") (name "/CHIP_IO_44") (class "Default")
      (node (ref "J11") (pin "8") (pinfunction "8_8") (pintype "passive"))
      (node (ref "JP6") (pin "13") (pinfunction "13_13") (pintype "passive"))
    )
    (net (code "47") (name "/CHIP_IO_45") (class "Default")
      (node (ref "J11") (pin "6") (pinfunction "6_6") (pintype "passive"))
      (node (ref "JP6") (pin "14") (pinfunction "14_14") (pintype "passive"))
    )
    (net (code "48") (name "/CHIP_IO_46") (class "Default")
      (node (ref "J11") (pin "4") (pinfunction "4_4") (pintype "passive"))
      (node (ref "JP6") (pin "15") (pinfunction "15_15") (pintype "passive"))
    )
    (net (code "49") (name "/CHIP_IO_47") (class "Default")
      (node (ref "J11") (pin "2") (pinfunction "2_2") (pintype "passive"))
      (node (ref "JP6") (pin "16") (pinfunction "16_16") (pintype "passive"))
    )
    (net (code "50") (name "/CHIP_IO_48") (class "Default")
      (node (ref "J12") (pin "16") (pinfunction "16_16") (pintype "passive"))
      (node (ref "JP8") (pin "1") (pinfunction "1_1") (pintype "passive"))
    )
    (net (code "51") (name "/CHIP_IO_49") (class "Default")
      (node (ref "J12") (pin "14") (pinfunction "14_14") (pintype "passive"))
      (node (ref "JP8") (pin "2") (pinfunction "2_2") (pintype "passive"))
    )
    (net (code "52") (name "/CHIP_IO_50") (class "Default")
      (node (ref "J12") (pin "12") (pinfunction "12_12") (pintype "passive"))
      (node (ref "JP8") (pin "3") (pinfunction "3_3") (pintype "passive"))
    )
    (net (code "53") (name "/CHIP_IO_51") (class "Default")
      (node (ref "J12") (pin "10") (pinfunction "10_10") (pintype "passive"))
      (node (ref "JP8") (pin "4") (pinfunction "4_4") (pintype "passive"))
    )
    (net (code "54") (name "/CHIP_IO_52") (class "Default")
      (node (ref "J12") (pin "8") (pinfunction "8_8") (pintype "passive"))
      (node (ref "JP8") (pin "5") (pinfunction "5_5") (pintype "passive"))
    )
    (net (code "55") (name "/CHIP_IO_53") (class "Default")
      (node (ref "J12") (pin "6") (pinfunction "6_6") (pintype "passive"))
      (node (ref "JP8") (pin "6") (pinfunction "6_6") (pintype "passive"))
    )
    (net (code "56") (name "/CHIP_IO_54") (class "Default")
      (node (ref "J12") (pin "4") (pinfunction "4_4") (pintype "passive"))
      (node (ref "JP8") (pin "7") (pinfunction "7_7") (pintype "passive"))
    )
    (net (code "57") (name "/CHIP_IO_55") (class "Default")
      (node (ref "J12") (pin "2") (pinfunction "2_2") (pintype "passive"))
      (node (ref "JP8") (pin "8") (pinfunction "8_8") (pintype "passive"))
    )
    (net (code "58") (name "/CHIP_IO_56") (class "Default")
      (node (ref "J13") (pin "16") (pinfunction "16_16") (pintype "passive"))
      (node (ref "JP8") (pin "9") (pinfunction "9_9") (pintype "passive"))
    )
    (net (code "59") (name "/CHIP_IO_57") (class "Default")
      (node (ref "J13") (pin "14") (pinfunction "14_14") (pintype "passive"))
      (node (ref "JP8") (pin "10") (pinfunction "10_10") (pintype "passive"))
    )
    (net (code "60") (name "/CHIP_IO_58") (class "Default")
      (node (ref "J13") (pin "12") (pinfunction "12_12") (pintype "passive"))
      (node (ref "JP8") (pin "11") (pinfunction "11_11") (pintype "passive"))
    )
    (net (code "61") (name "/CHIP_IO_59") (class "Default")
      (node (ref "J13") (pin "10") (pinfunction "10_10") (pintype "passive"))
      (node (ref "JP8") (pin "12") (pinfunction "12_12") (pintype "passive"))
    )
    (net (code "62") (name "/CHIP_IO_60") (class "Default")
      (node (ref "J13") (pin "8") (pinfunction "8_8") (pintype "passive"))
      (node (ref "JP8") (pin "13") (pinfunction "13_13") (pintype "passive"))
    )
    (net (code "63") (name "/CHIP_IO_61") (class "Default")
      (node (ref "J13") (pin "6") (pinfunction "6_6") (pintype "passive"))
      (node (ref "JP8") (pin "14") (pinfunction "14_14") (pintype "passive"))
    )
    (net (code "64") (name "/CHIP_IO_62") (class "Default")
      (node (ref "J13") (pin "4") (pinfunction "4_4") (pintype "passive"))
      (node (ref "JP8") (pin "15") (pinfunction "15_15") (pintype "passive"))
    )
    (net (code "65") (name "/CHIP_IO_63") (class "Default")
      (node (ref "J13") (pin "2") (pinfunction "2_2") (pintype "passive"))
      (node (ref "JP8") (pin "16") (pinfunction "16_16") (pintype "passive"))
    )
    (net (code "66") (name "/FPGA_HOST_EN") (class "Default")
      (node (ref "M1") (pin "Z5") (pinfunction "Z_BUS2_Z5") (pintype "passive"))
      (node (ref "P8") (pin "1") (pinfunction "1_1") (pintype "passive"))
    )
    (net (code "67") (name "/FPGA_IO_!OE") (class "Default")
      (node (ref "M1") (pin "Z4") (pinfunction "Z_BUS1_Z4") (pintype "passive"))
      (node (ref "P4") (pin "1") (pinfunction "1_1") (pintype "passive"))
    )
    (net (code "68") (name "/FPGA_IO_0") (class "Default")
      (node (ref "JP1") (pin "1") (pinfunction "1_1") (pintype "passive"))
      (node (ref "M1") (pin "Y15") (pinfunction "Y_BUS27_Y15") (pintype "passive"))
    )
    (net (code "69") (name "/FPGA_IO_1") (class "Default")
      (node (ref "JP1") (pin "2") (pinfunction "2_2") (pintype "passive"))
      (node (ref "M1") (pin "Y16") (pinfunction "Y_BUS26_Y16") (pintype "passive"))
    )
    (net (code "70") (name "/FPGA_IO_2") (class "Default")
      (node (ref "JP1") (pin "3") (pinfunction "3_3") (pintype "passive"))
      (node (ref "M1") (pin "Y17") (pinfunction "Y_BUS25_Y17") (pintype "passive"))
    )
    (net (code "71") (name "/FPGA_IO_3") (class "Default")
      (node (ref "JP1") (pin "4") (pinfunction "4_4") (pintype "passive"))
      (node (ref "M1") (pin "Y18") (pinfunction "Y_BUS24_Y18") (pintype "passive"))
    )
    (net (code "72") (name "/FPGA_IO_4") (class "Default")
      (node (ref "JP1") (pin "5") (pinfunction "5_5") (pintype "passive"))
      (node (ref "M1") (pin "Y21") (pinfunction "Y_BUS23_Y21") (pintype "passive"))
    )
    (net (code "73") (name "/FPGA_IO_5") (class "Default")
      (node (ref "JP1") (pin "6") (pinfunction "6_6") (pintype "passive"))
      (node (ref "M1") (pin "Y22") (pinfunction "Y_BUS22_Y22") (pintype "passive"))
    )
    (net (code "74") (name "/FPGA_IO_6") (class "Default")
      (node (ref "JP1") (pin "7") (pinfunction "7_7") (pintype "passive"))
      (node (ref "M1") (pin "Y23") (pinfunction "Y_BUS21_Y23") (pintype "passive"))
    )
    (net (code "75") (name "/FPGA_IO_7") (class "Default")
      (node (ref "JP1") (pin "8") (pinfunction "8_8") (pintype "passive"))
      (node (ref "M1") (pin "Y24") (pinfunction "Y_BUS20_Y24") (pintype "passive"))
    )
    (net (code "76") (name "/FPGA_IO_8") (class "Default")
      (node (ref "JP1") (pin "9") (pinfunction "9_9") (pintype "passive"))
      (node (ref "M1") (pin "Y25") (pinfunction "Y_BUS19_Y25") (pintype "passive"))
    )
    (net (code "77") (name "/FPGA_IO_9") (class "Default")
      (node (ref "JP1") (pin "10") (pinfunction "10_10") (pintype "passive"))
      (node (ref "M1") (pin "Y26") (pinfunction "Y_BUS18_Y26") (pintype "passive"))
    )
    (net (code "78") (name "/FPGA_IO_10") (class "Default")
      (node (ref "JP1") (pin "11") (pinfunction "11_11") (pintype "passive"))
      (node (ref "M1") (pin "Y27") (pinfunction "Y_BUS17_Y27") (pintype "passive"))
    )
    (net (code "79") (name "/FPGA_IO_11") (class "Default")
      (node (ref "JP1") (pin "12") (pinfunction "12_12") (pintype "passive"))
      (node (ref "M1") (pin "Y28") (pinfunction "Y_BUS16_Y28") (pintype "passive"))
    )
    (net (code "80") (name "/FPGA_IO_12") (class "Default")
      (node (ref "JP1") (pin "13") (pinfunction "13_13") (pintype "passive"))
      (node (ref "M1") (pin "Y29") (pinfunction "Y_BUS15_Y29") (pintype "passive"))
    )
    (net (code "81") (name "/FPGA_IO_13") (class "Default")
      (node (ref "JP1") (pin "14") (pinfunction "14_14") (pintype "passive"))
      (node (ref "M1") (pin "Y30") (pinfunction "Y_BUS14_Y30") (pintype "passive"))
    )
    (net (code "82") (name "/FPGA_IO_14") (class "Default")
      (node (ref "JP1") (pin "15") (pinfunction "15_15") (pintype "passive"))
      (node (ref "M1") (pin "Y33") (pinfunction "Y_BUS13_Y33") (pintype "passive"))
    )
    (net (code "83") (name "/FPGA_IO_15") (class "Default")
      (node (ref "JP1") (pin "16") (pinfunction "16_16") (pintype "passive"))
      (node (ref "M1") (pin "Y34") (pinfunction "Y_BUS12_Y34") (pintype "passive"))
    )
    (net (code "84") (name "/FPGA_IO_16") (class "Default")
      (node (ref "JP3") (pin "1") (pinfunction "1_1") (pintype "passive"))
      (node (ref "M1") (pin "Y35") (pinfunction "Y_BUS11_Y35") (pintype "passive"))
    )
    (net (code "85") (name "/FPGA_IO_17") (class "Default")
      (node (ref "JP3") (pin "2") (pinfunction "2_2") (pintype "passive"))
      (node (ref "M1") (pin "Y36") (pinfunction "Y_BUS10_Y36") (pintype "passive"))
    )
    (net (code "86") (name "/FPGA_IO_18") (class "Default")
      (node (ref "JP3") (pin "3") (pinfunction "3_3") (pintype "passive"))
      (node (ref "M1") (pin "Y37") (pinfunction "Y_BUS9_Y37") (pintype "passive"))
    )
    (net (code "87") (name "/FPGA_IO_19") (class "Default")
      (node (ref "JP3") (pin "4") (pinfunction "4_4") (pintype "passive"))
      (node (ref "M1") (pin "Y38") (pinfunction "Y_BUS8_Y38") (pintype "passive"))
    )
    (net (code "88") (name "/FPGA_IO_20") (class "Default")
      (node (ref "JP3") (pin "5") (pinfunction "5_5") (pintype "passive"))
      (node (ref "M1") (pin "Y39") (pinfunction "Y_BUS7_Y39") (pintype "passive"))
    )
    (net (code "89") (name "/FPGA_IO_21") (class "Default")
      (node (ref "JP3") (pin "6") (pinfunction "6_6") (pintype "passive"))
      (node (ref "M1") (pin "Y40") (pinfunction "Y_BUS6_Y40") (pintype "passive"))
    )
    (net (code "90") (name "/FPGA_IO_22") (class "Default")
      (node (ref "JP3") (pin "7") (pinfunction "7_7") (pintype "passive"))
      (node (ref "M1") (pin "Y43") (pinfunction "Y_BUS5_Y43") (pintype "passive"))
    )
    (net (code "91") (name "/FPGA_IO_23") (class "Default")
      (node (ref "JP3") (pin "8") (pinfunction "8_8") (pintype "passive"))
      (node (ref "M1") (pin "Y44") (pinfunction "Y_BUS4_Y44") (pintype "passive"))
    )
    (net (code "92") (name "/FPGA_IO_24") (class "Default")
      (node (ref "JP3") (pin "9") (pinfunction "9_9") (pintype "passive"))
      (node (ref "M1") (pin "Y45") (pinfunction "Y_BUS3_Y45") (pintype "passive"))
    )
    (net (code "93") (name "/FPGA_IO_25") (class "Default")
      (node (ref "JP3") (pin "10") (pinfunction "10_10") (pintype "passive"))
      (node (ref "M1") (pin "Y46") (pinfunction "Y_BUS2_Y46") (pintype "passive"))
    )
    (net (code "94") (name "/FPGA_IO_26") (class "Default")
      (node (ref "JP3") (pin "11") (pinfunction "11_11") (pintype "passive"))
      (node (ref "M1") (pin "Y47") (pinfunction "Y_BUS1_Y47") (pintype "passive"))
    )
    (net (code "95") (name "/FPGA_IO_27") (class "Default")
      (node (ref "JP3") (pin "12") (pinfunction "12_12") (pintype "passive"))
      (node (ref "M1") (pin "Y48") (pinfunction "Y_BUS0_Y48") (pintype "passive"))
    )
    (net (code "96") (name "/FPGA_IO_28") (class "Default")
      (node (ref "JP3") (pin "13") (pinfunction "13_13") (pintype "passive"))
      (node (ref "M1") (pin "X3") (pinfunction "X_BUS0_X3") (pintype "passive"))
    )
    (net (code "97") (name "/FPGA_IO_29") (class "Default")
      (node (ref "JP3") (pin "14") (pinfunction "14_14") (pintype "passive"))
      (node (ref "M1") (pin "X4") (pinfunction "X_BUS1_X4") (pintype "passive"))
    )
    (net (code "98") (name "/FPGA_IO_30") (class "Default")
      (node (ref "JP3") (pin "15") (pinfunction "15_15") (pintype "passive"))
      (node (ref "M1") (pin "X5") (pinfunction "X_BUS2_X5") (pintype "passive"))
    )
    (net (code "99") (name "/FPGA_IO_31") (class "Default")
      (node (ref "JP3") (pin "16") (pinfunction "16_16") (pintype "passive"))
      (node (ref "M1") (pin "X6") (pinfunction "X_BUS3_X6") (pintype "passive"))
    )
    (net (code "100") (name "/FPGA_IO_32") (class "Default")
      (node (ref "JP5") (pin "1") (pinfunction "1_1") (pintype "passive"))
      (node (ref "M1") (pin "X7") (pinfunction "X_BUS4_X7") (pintype "passive"))
    )
    (net (code "101") (name "/FPGA_IO_33") (class "Default")
      (node (ref "JP5") (pin "2") (pinfunction "2_2") (pintype "passive"))
      (node (ref "M1") (pin "X8") (pinfunction "X_BUS5_X8") (pintype "passive"))
    )
    (net (code "102") (name "/FPGA_IO_34") (class "Default")
      (node (ref "JP5") (pin "3") (pinfunction "3_3") (pintype "passive"))
      (node (ref "M1") (pin "X11") (pinfunction "X_BUS6_X11") (pintype "passive"))
    )
    (net (code "103") (name "/FPGA_IO_35") (class "Default")
      (node (ref "JP5") (pin "4") (pinfunction "4_4") (pintype "passive"))
      (node (ref "M1") (pin "X12") (pinfunction "X_BUS7_X12") (pintype "passive"))
    )
    (net (code "104") (name "/FPGA_IO_36") (class "Default")
      (node (ref "JP5") (pin "5") (pinfunction "5_5") (pintype "passive"))
      (node (ref "M1") (pin "X13") (pinfunction "X_BUS8_X13") (pintype "passive"))
    )
    (net (code "105") (name "/FPGA_IO_37") (class "Default")
      (node (ref "JP5") (pin "6") (pinfunction "6_6") (pintype "passive"))
      (node (ref "M1") (pin "X14") (pinfunction "X_BUS9_X14") (pintype "passive"))
    )
    (net (code "106") (name "/FPGA_IO_38") (class "Default")
      (node (ref "JP5") (pin "7") (pinfunction "7_7") (pintype "passive"))
      (node (ref "M1") (pin "X15") (pinfunction "X_BUS10_X15") (pintype "passive"))
    )
    (net (code "107") (name "/FPGA_IO_39") (class "Default")
      (node (ref "JP5") (pin "8") (pinfunction "8_8") (pintype "passive"))
      (node (ref "M1") (pin "X16") (pinfunction "X_BUS11_X16") (pintype "passive"))
    )
    (net (code "108") (name "/FPGA_IO_40") (class "Default")
      (node (ref "JP5") (pin "9") (pinfunction "9_9") (pintype "passive"))
      (node (ref "M1") (pin "X17") (pinfunction "X_BUS12_X17") (pintype "passive"))
    )
    (net (code "109") (name "/FPGA_IO_41") (class "Default")
      (node (ref "JP5") (pin "10") (pinfunction "10_10") (pintype "passive"))
      (node (ref "M1") (pin "X18") (pinfunction "X_BUS13_X18") (pintype "passive"))
    )
    (net (code "110") (name "/FPGA_IO_42") (class "Default")
      (node (ref "JP5") (pin "11") (pinfunction "11_11") (pintype "passive"))
      (node (ref "M1") (pin "X21") (pinfunction "X_BUS14_X21") (pintype "passive"))
    )
    (net (code "111") (name "/FPGA_IO_43") (class "Default")
      (node (ref "JP5") (pin "12") (pinfunction "12_12") (pintype "passive"))
      (node (ref "M1") (pin "X22") (pinfunction "X_BUS15_X22") (pintype "passive"))
    )
    (net (code "112") (name "/FPGA_IO_44") (class "Default")
      (node (ref "JP5") (pin "13") (pinfunction "13_13") (pintype "passive"))
      (node (ref "M1") (pin "X23") (pinfunction "X_BUS16_X23") (pintype "passive"))
    )
    (net (code "113") (name "/FPGA_IO_45") (class "Default")
      (node (ref "JP5") (pin "14") (pinfunction "14_14") (pintype "passive"))
      (node (ref "M1") (pin "X24") (pinfunction "X_BUS17_X24") (pintype "passive"))
    )
    (net (code "114") (name "/FPGA_IO_46") (class "Default")
      (node (ref "JP5") (pin "15") (pinfunction "15_15") (pintype "passive"))
      (node (ref "M1") (pin "X25") (pinfunction "X_BUS18_X25") (pintype "passive"))
    )
    (net (code "115") (name "/FPGA_IO_47") (class "Default")
      (node (ref "JP5") (pin "16") (pinfunction "16_16") (pintype "passive"))
      (node (ref "M1") (pin "X26") (pinfunction "X_BUS19_X26") (pintype "passive"))
    )
    (net (code "116") (name "/FPGA_IO_48") (class "Default")
      (node (ref "JP7") (pin "1") (pinfunction "1_1") (pintype "passive"))
      (node (ref "M1") (pin "X27") (pinfunction "X_BUS20_X27") (pintype "passive"))
    )
    (net (code "117") (name "/FPGA_IO_49") (class "Default")
      (node (ref "JP7") (pin "2") (pinfunction "2_2") (pintype "passive"))
      (node (ref "M1") (pin "X28") (pinfunction "X_BUS21_X28") (pintype "passive"))
    )
    (net (code "118") (name "/FPGA_IO_50") (class "Default")
      (node (ref "JP7") (pin "3") (pinfunction "3_3") (pintype "passive"))
      (node (ref "M1") (pin "X29") (pinfunction "X_BUS22_X29") (pintype "passive"))
    )
    (net (code "119") (name "/FPGA_IO_51") (class "Default")
      (node (ref "JP7") (pin "4") (pinfunction "4_4") (pintype "passive"))
      (node (ref "M1") (pin "X30") (pinfunction "X_BUS23_X30") (pintype "passive"))
    )
    (net (code "120") (name "/FPGA_IO_52") (class "Default")
      (node (ref "JP7") (pin "5") (pinfunction "5_5") (pintype "passive"))
      (node (ref "M1") (pin "X33") (pinfunction "X_BUS24_X33") (pintype "passive"))
    )
    (net (code "121") (name "/FPGA_IO_53") (class "Default")
      (node (ref "JP7") (pin "6") (pinfunction "6_6") (pintype "passive"))
      (node (ref "M1") (pin "X34") (pinfunction "X_BUS25_X34") (pintype "passive"))
    )
    (net (code "122") (name "/FPGA_IO_54") (class "Default")
      (node (ref "JP7") (pin "7") (pinfunction "7_7") (pintype "passive"))
      (node (ref "M1") (pin "X35") (pinfunction "X_BUS26_X35") (pintype "passive"))
    )
    (net (code "123") (name "/FPGA_IO_55") (class "Default")
      (node (ref "JP7") (pin "8") (pinfunction "8_8") (pintype "passive"))
      (node (ref "M1") (pin "X36") (pinfunction "X_BUS27_X36") (pintype "passive"))
    )
    (net (code "124") (name "/FPGA_IO_56") (class "Default")
      (node (ref "JP7") (pin "9") (pinfunction "9_9") (pintype "passive"))
      (node (ref "M1") (pin "X37") (pinfunction "X_BUS28_X37") (pintype "passive"))
    )
    (net (code "125") (name "/FPGA_IO_57") (class "Default")
      (node (ref "JP7") (pin "10") (pinfunction "10_10") (pintype "passive"))
      (node (ref "M1") (pin "X38") (pinfunction "X_BUS29_X38") (pintype "passive"))
    )
    (net (code "126") (name "/FPGA_IO_58") (class "Default")
      (node (ref "JP7") (pin "11") (pinfunction "11_11") (pintype "passive"))
      (node (ref "M1") (pin "X39") (pinfunction "X_BUS30_X39") (pintype "passive"))
    )
    (net (code "127") (name "/FPGA_IO_59") (class "Default")
      (node (ref "JP7") (pin "12") (pinfunction "12_12") (pintype "passive"))
      (node (ref "M1") (pin "X40") (pinfunction "X_BUS31_X40") (pintype "passive"))
    )
    (net (code "128") (name "/FPGA_IO_60") (class "Default")
      (node (ref "JP7") (pin "13") (pinfunction "13_13") (pintype "passive"))
      (node (ref "M1") (pin "X43") (pinfunction "X_BUS32_X43") (pintype "passive"))
    )
    (net (code "129") (name "/FPGA_IO_61") (class "Default")
      (node (ref "JP7") (pin "14") (pinfunction "14_14") (pintype "passive"))
      (node (ref "M1") (pin "X44") (pinfunction "X_BUS33_X44") (pintype "passive"))
    )
    (net (code "130") (name "/FPGA_IO_62") (class "Default")
      (node (ref "JP7") (pin "15") (pinfunction "15_15") (pintype "passive"))
      (node (ref "M1") (pin "X45") (pinfunction "X_BUS34_X45") (pintype "passive"))
    )
    (net (code "131") (name "/FPGA_IO_63") (class "Default")
      (node (ref "JP7") (pin "16") (pinfunction "16_16") (pintype "passive"))
      (node (ref "M1") (pin "X46") (pinfunction "X_BUS35_X46") (pintype "passive"))
    )
    (net (code "133") (name "/FPGA_PLL_EN") (class "Default")
      (node (ref "M1") (pin "Z3") (pinfunction "Z_BUS0_Z3") (pintype "passive"))
      (node (ref "P5") (pin "1") (pinfunction "1_1") (pintype "passive"))
    )
    (net (code "134") (name "/LOADSW_ON_HOST") (class "Default")
      (node (ref "P8") (pin "2") (pinfunction "2_2") (pintype "passive"))
      (node (ref "R22") (pin "2") (pinfunction "2_2") (pintype "passive"))
      (node (ref "R23") (pin "1") (pinfunction "1_1") (pintype "passive"))
      (node (ref "U7") (pin "3") (pinfunction "ON_3") (pintype "input"))
    )
    (net (code "135") (name "/LOADSW_ON_PLL") (class "Default")
      (node (ref "P5") (pin "2") (pinfunction "2_2") (pintype "passive"))
      (node (ref "R20") (pin "2") (pinfunction "2_2") (pintype "passive"))
      (node (ref "R21") (pin "1") (pinfunction "1_1") (pintype "passive"))
      (node (ref "U5") (pin "3") (pinfunction "ON_3") (pintype "input"))
    )
    (net (code "136") (name "/LV_DIR_0") (class "Default")
      (node (ref "M1") (pin "Y5") (pinfunction "Y_BUS35_Y5") (pintype "passive"))
    )
    (net (code "137") (name "/LV_DIR_1") (class "Default")
      (node (ref "M1") (pin "Y6") (pinfunction "Y_BUS34_Y6") (pintype "passive"))
    )
    (net (code "138") (name "/LV_DIR_2") (class "Default")
      (node (ref "M1") (pin "Y7") (pinfunction "Y_BUS33_Y7") (pintype "passive"))
    )
    (net (code "139") (name "/LV_DIR_3") (class "Default")
      (node (ref "M1") (pin "Y8") (pinfunction "Y_BUS32_Y8") (pintype "passive"))
    )
    (net (code "140") (name "/LV_DIR_4") (class "Default")
      (node (ref "M1") (pin "Y11") (pinfunction "Y_BUS31_Y11") (pintype "passive"))
    )
    (net (code "141") (name "/LV_DIR_5") (class "Default")
      (node (ref "M1") (pin "Y12") (pinfunction "Y_BUS30_Y12") (pintype "passive"))
    )
    (net (code "142") (name "/LV_DIR_6") (class "Default")
      (node (ref "M1") (pin "Y13") (pinfunction "Y_BUS29_Y13") (pintype "passive"))
    )
    (net (code "143") (name "/LV_DIR_7") (class "Default")
      (node (ref "M1") (pin "Y14") (pinfunction "Y_BUS28_Y14") (pintype "passive"))
    )
    (net (code "144") (name "/PAD1") (class "Default")
      (node (ref "C10") (pin "1") (pinfunction "1_1") (pintype "passive"))
      (node (ref "MH1") (pin "PAD") (pinfunction "PAD_PAD") (pintype "passive"))
      (node (ref "R9") (pin "1") (pinfunction "1_1") (pintype "passive"))
    )
    (net (code "145") (name "/PAD2") (class "Default")
      (node (ref "C13") (pin "1") (pinfunction "1_1") (pintype "passive"))
      (node (ref "MH2") (pin "PAD") (pinfunction "PAD_PAD") (pintype "passive"))
      (node (ref "R10") (pin "1") (pinfunction "1_1") (pintype "passive"))
    )
    (net (code "146") (name "/PAD3") (class "Default")
      (node (ref "C14") (pin "1") (pinfunction "1_1") (pintype "passive"))
      (node (ref "MH3") (pin "PAD") (pinfunction "PAD_PAD") (pintype "passive"))
      (node (ref "R11") (pin "1") (pinfunction "1_1") (pintype "passive"))
    )
    (net (code "147") (name "/PAD4") (class "Default")
      (node (ref "C17") (pin "1") (pinfunction "1_1") (pintype "passive"))
      (node (ref "MH4") (pin "PAD") (pinfunction "PAD_PAD") (pintype "passive"))
      (node (ref "R12") (pin "1") (pinfunction "1_1") (pintype "passive"))
    )
    (net (code "148") (name "/PAD5") (class "Default")
      (node (ref "C18") (pin "1") (pinfunction "1_1") (pintype "passive"))
      (node (ref "MH5") (pin "PAD") (pinfunction "PAD_PAD") (pintype "passive"))
      (node (ref "R13") (pin "1") (pinfunction "1_1") (pintype "passive"))
    )
    (net (code "149") (name "/PAD6") (class "Default")
      (node (ref "C19") (pin "1") (pinfunction "1_1") (pintype "passive"))
      (node (ref "MH6") (pin "PAD") (pinfunction "PAD_PAD") (pintype "passive"))
      (node (ref "R14") (pin "1") (pinfunction "1_1") (pintype "passive"))
    )
    (net (code "150") (name "/PP_P3V3_LDO") (class "Default")
      (node (ref "C15") (pin "1") (pinfunction "1_1") (pintype "passive"))
      (node (ref "C16") (pin "1") (pinfunction "1_1") (pintype "passive"))
      (node (ref "P3") (pin "1") (pinfunction "1_1") (pintype "passive"))
      (node (ref "U4") (pin "4") (pinfunction "VOUT_4") (pintype "power_in"))
    )
    (net (code "151") (name "/PP_P3V3_LED") (class "Default")
      (node (ref "P6") (pin "2") (pinfunction "2_2") (pintype "passive"))
      (node (ref "R15") (pin "2") (pinfunction "2_2") (pintype "passive"))
      (node (ref "R16") (pin "2") (pinfunction "2_2") (pintype "passive"))
      (node (ref "R17") (pin "2") (pinfunction "2_2") (pintype "passive"))
      (node (ref "R24") (pin "2") (pinfunction "2_2") (pintype "passive"))
    )
    (net (code "152") (name "/PP_P5V0_LDO") (class "Default")
      (node (ref "C11") (pin "1") (pinfunction "1_1") (pintype "passive"))
      (node (ref "C12") (pin "1") (pinfunction "1_1") (pintype "passive"))
      (node (ref "U3") (pin "4") (pinfunction "VOUT_4") (pintype "power_in"))
      (node (ref "U5") (pin "4") (pinfunction "VIN_4") (pintype "power_in"))
      (node (ref "U5") (pin "6") (pinfunction "VIN_6") (pintype "power_in"))
    )
    (net (code "153") (name "/PP_P5V0_LDO_HOST") (class "Default")
      (node (ref "C24") (pin "1") (pinfunction "1_1") (pintype "passive"))
      (node (ref "C25") (pin "1") (pinfunction "1_1") (pintype "passive"))
      (node (ref "U6") (pin "4") (pinfunction "VOUT_4") (pintype "power_in"))
      (node (ref "U7") (pin "4") (pinfunction "VIN_4") (pintype "power_in"))
      (node (ref "U7") (pin "6") (pinfunction "VIN_6") (pintype "power_in"))
    )
    (net (code "154") (name "/PP_P5V0_LDSW") (class "Default")
      (node (ref "P1") (pin "1") (pinfunction "1_1") (pintype "passive"))
      (node (ref "U5") (pin "1") (pinfunction "VOUT_1") (pintype "power_in"))
    )
    (net (code "155") (name "/VIN_UNREG") (class "Default")
      (node (ref "D1") (pin "2") (pinfunction "A_2") (pintype "passive"))
      (node (ref "D2") (pin "1") (pinfunction "1_1") (pintype "passive"))
      (node (ref "J1") (pin "1") (pinfunction "1_1") (pintype "passive"))
      (node (ref "J14") (pin "2") (pinfunction "2_2") (pintype "passive"))
      (node (ref "J14") (pin "3") (pinfunction "3_3") (pintype "passive"))
      (node (ref "J2") (pin "1") (pinfunction "1_1") (pintype "passive"))
      (node (ref "P2") (pin "2") (pinfunction "2_2") (pintype "passive"))
      (node (ref "TP6") (pin "1") (pintype "passive"))
    )
    (net (code "156") (name "/VIN_UNREG_D") (class "Default")
      (node (ref "C20") (pin "1") (pinfunction "1_1") (pintype "passive"))
      (node (ref "C21") (pin "1") (pinfunction "1_1") (pintype "passive"))
      (node (ref "C22") (pin "1") (pinfunction "1_1") (pintype "passive"))
      (node (ref "C23") (pin "1") (pinfunction "1_1") (pintype "passive"))
      (node (ref "D1") (pin "1") (pinfunction "C_1") (pintype "passive"))
      (node (ref "U3") (pin "3") (pinfunction "VIN_3") (pintype "power_in"))
      (node (ref "U4") (pin "3") (pinfunction "VIN_3") (pintype "power_in"))
      (node (ref "U6") (pin "3") (pinfunction "VIN_3") (pintype "power_in"))
    )
    (net (code "157") (name "GND") (class "Default")
      (node (ref "C10") (pin "2") (pinfunction "2_2") (pintype "passive"))
      (node (ref "C11") (pin "2") (pinfunction "2_2") (pintype "passive"))
      (node (ref "C12") (pin "2") (pinfunction "2_2") (pintype "passive"))
      (node (ref "C13") (pin "2") (pinfunction "2_2") (pintype "passive"))
      (node (ref "C14") (pin "2") (pinfunction "2_2") (pintype "passive"))
      (node (ref "C15") (pin "2") (pinfunction "2_2") (pintype "passive"))
      (node (ref "C16") (pin "2") (pinfunction "2_2") (pintype "passive"))
      (node (ref "C17") (pin "2") (pinfunction "2_2") (pintype "passive"))
      (node (ref "C18") (pin "2") (pinfunction "2_2") (pintype "passive"))
      (node (ref "C19") (pin "2") (pinfunction "2_2") (pintype "passive"))
      (node (ref "C20") (pin "2") (pinfunction "2_2") (pintype "passive"))
      (node (ref "C21") (pin "2") (pinfunction "2_2") (pintype "passive"))
      (node (ref "C22") (pin "2") (pinfunction "2_2") (pintype "passive"))
      (node (ref "C23") (pin "2") (pinfunction "2_2") (pintype "passive"))
      (node (ref "C24") (pin "2") (pinfunction "2_2") (pintype "passive"))
      (node (ref "C25") (pin "2") (pinfunction "2_2") (pintype "passive"))
      (node (ref "D2") (pin "2") (pinfunction "2_2") (pintype "passive"))
      (node (ref "DS2") (pin "2") (pinfunction "K_2") (pintype "passive"))
      (node (ref "J10") (pin "1") (pinfunction "1_1") (pintype "passive"))
      (node (ref "J10") (pin "11") (pinfunction "11_11") (pintype "passive"))
      (node (ref "J10") (pin "13") (pinfunction "13_13") (pintype "passive"))
      (node (ref "J10") (pin "15") (pinfunction "15_15") (pintype "passive"))
      (node (ref "J10") (pin "3") (pinfunction "3_3") (pintype "passive"))
      (node (ref "J10") (pin "5") (pinfunction "5_5") (pintype "passive"))
      (node (ref "J10") (pin "7") (pinfunction "7_7") (pintype "passive"))
      (node (ref "J10") (pin "9") (pinfunction "9_9") (pintype "passive"))
      (node (ref "J11") (pin "1") (pinfunction "1_1") (pintype "passive"))
      (node (ref "J11") (pin "11") (pinfunction "11_11") (pintype "passive"))
      (node (ref "J11") (pin "13") (pinfunction "13_13") (pintype "passive"))
      (node (ref "J11") (pin "15") (pinfunction "15_15") (pintype "passive"))
      (node (ref "J11") (pin "3") (pinfunction "3_3") (pintype "passive"))
      (node (ref "J11") (pin "5") (pinfunction "5_5") (pintype "passive"))
      (node (ref "J11") (pin "7") (pinfunction "7_7") (pintype "passive"))
      (node (ref "J11") (pin "9") (pinfunction "9_9") (pintype "passive"))
      (node (ref "J12") (pin "1") (pinfunction "1_1") (pintype "passive"))
      (node (ref "J12") (pin "11") (pinfunction "11_11") (pintype "passive"))
      (node (ref "J12") (pin "13") (pinfunction "13_13") (pintype "passive"))
      (node (ref "J12") (pin "15") (pinfunction "15_15") (pintype "passive"))
      (node (ref "J12") (pin "3") (pinfunction "3_3") (pintype "passive"))
      (node (ref "J12") (pin "5") (pinfunction "5_5") (pintype "passive"))
      (node (ref "J12") (pin "7") (pinfunction "7_7") (pintype "passive"))
      (node (ref "J12") (pin "9") (pinfunction "9_9") (pintype "passive"))
      (node (ref "J13") (pin "1") (pinfunction "1_1") (pintype "passive"))
      (node (ref "J13") (pin "11") (pinfunction "11_11") (pintype "passive"))
      (node (ref "J13") (pin "13") (pinfunction "13_13") (pintype "passive"))
      (node (ref "J13") (pin "15") (pinfunction "15_15") (pintype "passive"))
      (node (ref "J13") (pin "3") (pinfunction "3_3") (pintype "passive"))
      (node (ref "J13") (pin "5") (pinfunction "5_5") (pintype "passive"))
      (node (ref "J13") (pin "7") (pinfunction "7_7") (pintype "passive"))
      (node (ref "J13") (pin "9") (pinfunction "9_9") (pintype "passive"))
      (node (ref "J14") (pin "1") (pinfunction "1_1") (pintype "passive"))
      (node (ref "J14") (pin "4") (pinfunction "MNT_1_4") (pintype "passive"))
      (node (ref "J14") (pin "5") (pinfunction "MNT_2_5") (pintype "passive"))
      (node (ref "J3") (pin "1") (pinfunction "1_1") (pintype "passive"))
      (node (ref "J4") (pin "1") (pinfunction "1_1") (pintype "passive"))
      (node (ref "J6") (pin "1") (pinfunction "1_1") (pintype "passive"))
      (node (ref "J6") (pin "11") (pinfunction "11_11") (pintype "passive"))
      (node (ref "J6") (pin "13") (pinfunction "13_13") (pintype "passive"))
      (node (ref "J6") (pin "15") (pinfunction "15_15") (pintype "passive"))
      (node (ref "J6") (pin "3") (pinfunction "3_3") (pintype "passive"))
      (node (ref "J6") (pin "5") (pinfunction "5_5") (pintype "passive"))
      (node (ref "J6") (pin "7") (pinfunction "7_7") (pintype "passive"))
      (node (ref "J6") (pin "9") (pinfunction "9_9") (pintype "passive"))
      (node (ref "J7") (pin "1") (pinfunction "1_1") (pintype "passive"))
      (node (ref "J7") (pin "11") (pinfunction "11_11") (pintype "passive"))
      (node (ref "J7") (pin "13") (pinfunction "13_13") (pintype "passive"))
      (node (ref "J7") (pin "15") (pinfunction "15_15") (pintype "passive"))
      (node (ref "J7") (pin "3") (pinfunction "3_3") (pintype "passive"))
      (node (ref "J7") (pin "5") (pinfunction "5_5") (pintype "passive"))
      (node (ref "J7") (pin "7") (pinfunction "7_7") (pintype "passive"))
      (node (ref "J7") (pin "9") (pinfunction "9_9") (pintype "passive"))
      (node (ref "J8") (pin "1") (pinfunction "1_1") (pintype "passive"))
      (node (ref "J8") (pin "11") (pinfunction "11_11") (pintype "passive"))
      (node (ref "J8") (pin "13") (pinfunction "13_13") (pintype "passive"))
      (node (ref "J8") (pin "15") (pinfunction "15_15") (pintype "passive"))
      (node (ref "J8") (pin "3") (pinfunction "3_3") (pintype "passive"))
      (node (ref "J8") (pin "5") (pinfunction "5_5") (pintype "passive"))
      (node (ref "J8") (pin "7") (pinfunction "7_7") (pintype "passive"))
      (node (ref "J8") (pin "9") (pinfunction "9_9") (pintype "passive"))
      (node (ref "J9") (pin "1") (pinfunction "1_1") (pintype "passive"))
      (node (ref "J9") (pin "11") (pinfunction "11_11") (pintype "passive"))
      (node (ref "J9") (pin "13") (pinfunction "13_13") (pintype "passive"))
      (node (ref "J9") (pin "15") (pinfunction "15_15") (pintype "passive"))
      (node (ref "J9") (pin "3") (pinfunction "3_3") (pintype "passive"))
      (node (ref "J9") (pin "5") (pinfunction "5_5") (pintype "passive"))
      (node (ref "J9") (pin "7") (pinfunction "7_7") (pintype "passive"))
      (node (ref "J9") (pin "9") (pinfunction "9_9") (pintype "passive"))
      (node (ref "M1") (pin "X1") (pinfunction "DGND_X1") (pintype "power_in"))
      (node (ref "M1") (pin "X19") (pinfunction "DGND_X19") (pintype "power_in"))
      (node (ref "M1") (pin "X2") (pinfunction "DGND_X2") (pintype "power_in"))
      (node (ref "M1") (pin "X20") (pinfunction "DGND_X20") (pintype "power_in"))
      (node (ref "M1") (pin "X31") (pinfunction "DGND_X31") (pintype "power_in"))
      (node (ref "M1") (pin "X32") (pinfunction "DGND_X32") (pintype "power_in"))
      (node (ref "M1") (pin "X49") (pinfunction "DGND_X49") (pintype "power_in"))
      (node (ref "M1") (pin "X50") (pinfunction "DGND_X50") (pintype "power_in"))
      (node (ref "M1") (pin "Y1") (pinfunction "DGND_Y1") (pintype "power_in"))
      (node (ref "M1") (pin "Y19") (pinfunction "DGND_Y19") (pintype "power_in"))
      (node (ref "M1") (pin "Y2") (pinfunction "DGND_Y2") (pintype "power_in"))
      (node (ref "M1") (pin "Y20") (pinfunction "DGND_Y20") (pintype "power_in"))
      (node (ref "M1") (pin "Y31") (pinfunction "DGND_Y31") (pintype "power_in"))
      (node (ref "M1") (pin "Y32") (pinfunction "DGND_Y32") (pintype "power_in"))
      (node (ref "M1") (pin "Y49") (pinfunction "DGND_Y49") (pintype "power_in"))
      (node (ref "M1") (pin "Y50") (pinfunction "DGND_Y50") (pintype "power_in"))
      (node (ref "M1") (pin "Z19") (pinfunction "DGND_Z19") (pintype "power_in"))
      (node (ref "M1") (pin "Z20") (pinfunction "DGND_Z20") (pintype "power_in"))
      (node (ref "P2") (pin "1") (pinfunction "1_1") (pintype "passive"))
      (node (ref "P7") (pin "1") (pinfunction "1_1") (pintype "passive"))
      (node (ref "PCBA1") (pin "3") (pinfunction "GND_3") (pintype "passive"))
      (node (ref "PCBA1") (pin "4") (pinfunction "GND_4") (pintype "passive"))
      (node (ref "PCBA1") (pin "6") (pinfunction "GND_6") (pintype "passive"))
      (node (ref "PCBA1") (pin "MH") (pinfunction "GND_MH") (pintype "passive"))
      (node (ref "Q1") (pin "2") (pinfunction "S_2") (pintype "passive"))
      (node (ref "Q2") (pin "2") (pinfunction "S_2") (pintype "passive"))
      (node (ref "Q3") (pin "2") (pinfunction "S_2") (pintype "passive"))
      (node (ref "R10") (pin "2") (pinfunction "2_2") (pintype "passive"))
      (node (ref "R11") (pin "2") (pinfunction "2_2") (pintype "passive"))
      (node (ref "R12") (pin "2") (pinfunction "2_2") (pintype "passive"))
      (node (ref "R13") (pin "2") (pinfunction "2_2") (pintype "passive"))
      (node (ref "R14") (pin "2") (pinfunction "2_2") (pintype "passive"))
      (node (ref "R18") (pin "2") (pinfunction "2_2") (pintype "passive"))
      (node (ref "R21") (pin "2") (pinfunction "2_2") (pintype "passive"))
      (node (ref "R23") (pin "2") (pinfunction "2_2") (pintype "passive"))
      (node (ref "R9") (pin "2") (pinfunction "2_2") (pintype "passive"))
      (node (ref "TP3") (pin "1") (pintype "passive"))
      (node (ref "TP4") (pin "1") (pintype "passive"))
      (node (ref "TP5") (pin "1") (pintype "passive"))
      (node (ref "U3") (pin "1") (pinfunction "GND_1") (pintype "power_in"))
      (node (ref "U4") (pin "1") (pinfunction "GND_1") (pintype "power_in"))
      (node (ref "U5") (pin "2") (pinfunction "GND_2") (pintype "power_in"))
      (node (ref "U5") (pin "5") (pinfunction "GND_5") (pintype "power_in"))
      (node (ref "U6") (pin "1") (pinfunction "GND_1") (pintype "power_in"))
      (node (ref "U7") (pin "2") (pinfunction "GND_2") (pintype "power_in"))
      (node (ref "U7") (pin "5") (pinfunction "GND_5") (pintype "power_in"))
    )
    (net (code "158") (name "Net-(DS1-A)") (class "Default")
      (node (ref "DS1") (pin "1") (pinfunction "A_1") (pintype "passive"))
      (node (ref "R15") (pin "1") (pinfunction "1_1") (pintype "passive"))
    )
    (net (code "159") (name "Net-(DS1-K)") (class "Default")
      (node (ref "DS1") (pin "2") (pinfunction "K_2") (pintype "passive"))
      (node (ref "Q1") (pin "3") (pinfunction "D_3") (pintype "passive"))
    )
    (net (code "160") (name "Net-(DS2-A)") (class "Default")
      (node (ref "DS2") (pin "1") (pinfunction "A_1") (pintype "passive"))
      (node (ref "R16") (pin "1") (pinfunction "1_1") (pintype "passive"))
    )
    (net (code "161") (name "Net-(DS3-A)") (class "Default")
      (node (ref "DS3") (pin "1") (pinfunction "A_1") (pintype "passive"))
      (node (ref "R17") (pin "1") (pinfunction "1_1") (pintype "passive"))
    )
    (net (code "162") (name "Net-(DS3-K)") (class "Default")
      (node (ref "DS3") (pin "2") (pinfunction "K_2") (pintype "passive"))
      (node (ref "Q2") (pin "3") (pinfunction "D_3") (pintype "passive"))
    )
    (net (code "163") (name "Net-(DS4-A)") (class "Default")
      (node (ref "DS4") (pin "1") (pinfunction "A_1") (pintype "passive"))
      (node (ref "R24") (pin "1") (pinfunction "1_1") (pintype "passive"))
    )
    (net (code "164") (name "Net-(DS4-K)") (class "Default")
      (node (ref "DS4") (pin "2") (pinfunction "K_2") (pintype "passive"))
      (node (ref "Q3") (pin "3") (pinfunction "D_3") (pintype "passive"))
    )
    (net (code "165") (name "PP_P1V8_IO_DVDD") (class "Default")
      (node (ref "Q1") (pin "1") (pinfunction "G_1") (pintype "passive"))
    )
    (net (code "166") (name "PP_P3V3_IO_FPGA") (class "Default")
      (node (ref "M1") (pin "X10") (pinfunction "+3.3VDD_X10") (pintype "power_in"))
      (node (ref "M1") (pin "X41") (pinfunction "+3.3VDD_X41") (pintype "power_in"))
      (node (ref "M1") (pin "X42") (pinfunction "+3.3VDD_X42") (pintype "power_in"))
      (node (ref "M1") (pin "X9") (pinfunction "+3.3VDD_X9") (pintype "power_in"))
      (node (ref "M1") (pin "Y10") (pinfunction "+3.3VDD_Y10") (pintype "power_in"))
      (node (ref "M1") (pin "Y41") (pinfunction "+3.3VDD_Y41") (pintype "power_in"))
      (node (ref "M1") (pin "Y42") (pinfunction "+3.3VDD_Y42") (pintype "power_in"))
      (node (ref "M1") (pin "Y9") (pinfunction "+3.3VDD_Y9") (pintype "power_in"))
      (node (ref "M1") (pin "Z1") (pinfunction "+3.3VDD_Z1") (pintype "power_in"))
      (node (ref "M1") (pin "Z2") (pinfunction "+3.3VDD_Z2") (pintype "power_in"))
      (node (ref "P3") (pin "2") (pinfunction "2_2") (pintype "passive"))
      (node (ref "P6") (pin "1") (pinfunction "1_1") (pintype "passive"))
      (node (ref "R20") (pin "1") (pinfunction "1_1") (pintype "passive"))
      (node (ref "R22") (pin "1") (pinfunction "1_1") (pintype "passive"))
      (node (ref "R7") (pin "1") (pinfunction "1_1") (pintype "passive"))
    )
    (net (code "167") (name "PP_P5V0_LDSW_HOST") (class "Default")
      (node (ref "P7") (pin "2") (pinfunction "2_2") (pintype "passive"))
      (node (ref "Q3") (pin "1") (pinfunction "G_1") (pintype "passive"))
      (node (ref "U7") (pin "1") (pinfunction "VOUT_1") (pintype "power_in"))
    )
    (net (code "168") (name "PP_P5V0_PLL") (class "Default")
      (node (ref "P1") (pin "2") (pinfunction "2_2") (pintype "passive"))
      (node (ref "PCBA1") (pin "1") (pinfunction "VIN_MLB_1") (pintype "passive"))
      (node (ref "PCBA1") (pin "2") (pinfunction "VIN_MLB_2") (pintype "passive"))
      (node (ref "Q2") (pin "1") (pinfunction "G_1") (pintype "passive"))
    )
    (net (code "169") (name "unconnected-(M1A-SYS_CLK4-PadX48)") (class "Default")
      (node (ref "M1") (pin "X48") (pinfunction "SYS_CLK4_X48") (pintype "passive"))
    )
    (net (code "170") (name "unconnected-(M1A-X_CLK1-PadX47)") (class "Default")
      (node (ref "M1") (pin "X47") (pinfunction "X_CLK1_X47") (pintype "passive"))
    )
    (net (code "171") (name "unconnected-(M1B-SYS_CLK5-PadY3)") (class "Default")
      (node (ref "M1") (pin "Y3") (pinfunction "SYS_CLK5_Y3") (pintype "passive"))
    )
    (net (code "172") (name "unconnected-(M1B-Y_CLK1-PadY4)") (class "Default")
      (node (ref "M1") (pin "Y4") (pinfunction "Y_CLK1_Y4") (pintype "passive"))
    )
    (net (code "173") (name "unconnected-(M1C-Z_BUS3-PadZ6)") (class "Default")
      (node (ref "M1") (pin "Z6") (pinfunction "Z_BUS3_Z6") (pintype "passive"))
    )
    (net (code "174") (name "unconnected-(M1C-Z_BUS4-PadZ7)") (class "Default")
      (node (ref "M1") (pin "Z7") (pinfunction "Z_BUS4_Z7") (pintype "passive"))
    )
    (net (code "175") (name "unconnected-(M1C-Z_BUS5-PadZ8)") (class "Default")
      (node (ref "M1") (pin "Z8") (pinfunction "Z_BUS5_Z8") (pintype "passive"))
    )
    (net (code "176") (name "unconnected-(M1C-Z_BUS6-PadZ9)") (class "Default")
      (node (ref "M1") (pin "Z9") (pinfunction "Z_BUS6_Z9") (pintype "passive"))
    )
    (net (code "177") (name "unconnected-(M1C-Z_BUS7-PadZ10)") (class "Default")
      (node (ref "M1") (pin "Z10") (pinfunction "Z_BUS7_Z10") (pintype "passive"))
    )
    (net (code "178") (name "unconnected-(M1C-Z_BUS8-PadZ11)") (class "Default")
      (node (ref "M1") (pin "Z11") (pinfunction "Z_BUS8_Z11") (pintype "passive"))
    )
    (net (code "179") (name "unconnected-(M1C-Z_BUS9-PadZ12)") (class "Default")
      (node (ref "M1") (pin "Z12") (pinfunction "Z_BUS9_Z12") (pintype "passive"))
    )
    (net (code "180") (name "unconnected-(M1C-Z_BUS10-PadZ13)") (class "Default")
      (node (ref "M1") (pin "Z13") (pinfunction "Z_BUS10_Z13") (pintype "passive"))
    )
    (net (code "181") (name "unconnected-(M1C-Z_BUS11-PadZ14)") (class "Default")
      (node (ref "M1") (pin "Z14") (pinfunction "Z_BUS11_Z14") (pintype "passive"))
    )
    (net (code "182") (name "unconnected-(M1C-Z_BUS12-PadZ15)") (class "Default")
      (node (ref "M1") (pin "Z15") (pinfunction "Z_BUS12_Z15") (pintype "passive"))
    )
    (net (code "183") (name "unconnected-(M1C-Z_BUS13-PadZ16)") (class "Default")
      (node (ref "M1") (pin "Z16") (pinfunction "Z_BUS13_Z16") (pintype "passive"))
    )
    (net (code "184") (name "unconnected-(M1C-Z_CLK1-PadZ17)") (class "Default")
      (node (ref "M1") (pin "Z17") (pinfunction "Z_CLK1_Z17") (pintype "passive"))
    )
    (net (code "185") (name "unconnected-(M1C-Z_CLK2-PadZ18)") (class "Default")
      (node (ref "M1") (pin "Z18") (pinfunction "Z_CLK2_Z18") (pintype "passive"))
    )
    (net (code "186") (name "unconnected-(PCBA1-HW_SW_CTRL-Pad8)") (class "Default")
      (node (ref "PCBA1") (pin "8") (pinfunction "HW_SW_CTRL_8") (pintype "passive"))
    )
    (net (code "187") (name "unconnected-(PCBA1-SCL-Pad10)") (class "Default")
      (node (ref "PCBA1") (pin "10") (pinfunction "SCL_10") (pintype "passive"))
    )
    (net (code "188") (name "unconnected-(PCBA1-SDA-Pad9)") (class "Default")
      (node (ref "PCBA1") (pin "9") (pinfunction "SDA_9") (pintype "passive"))
    )
    (net (code "189") (name "unconnected-(PCBA1-STATUS0-Pad7)") (class "Default")
      (node (ref "PCBA1") (pin "7") (pinfunction "STATUS0_7") (pintype "passive"))
    )
    (net (code "190") (name "unconnected-(PCBA1-STATUS1-Pad5)") (class "Default")
      (node (ref "PCBA1") (pin "5") (pinfunction "STATUS1_5") (pintype "passive"))
    )
  )
)
